# CyDAQ_schematic.net
KiCad netlist of a schematic drawn in EAGLE
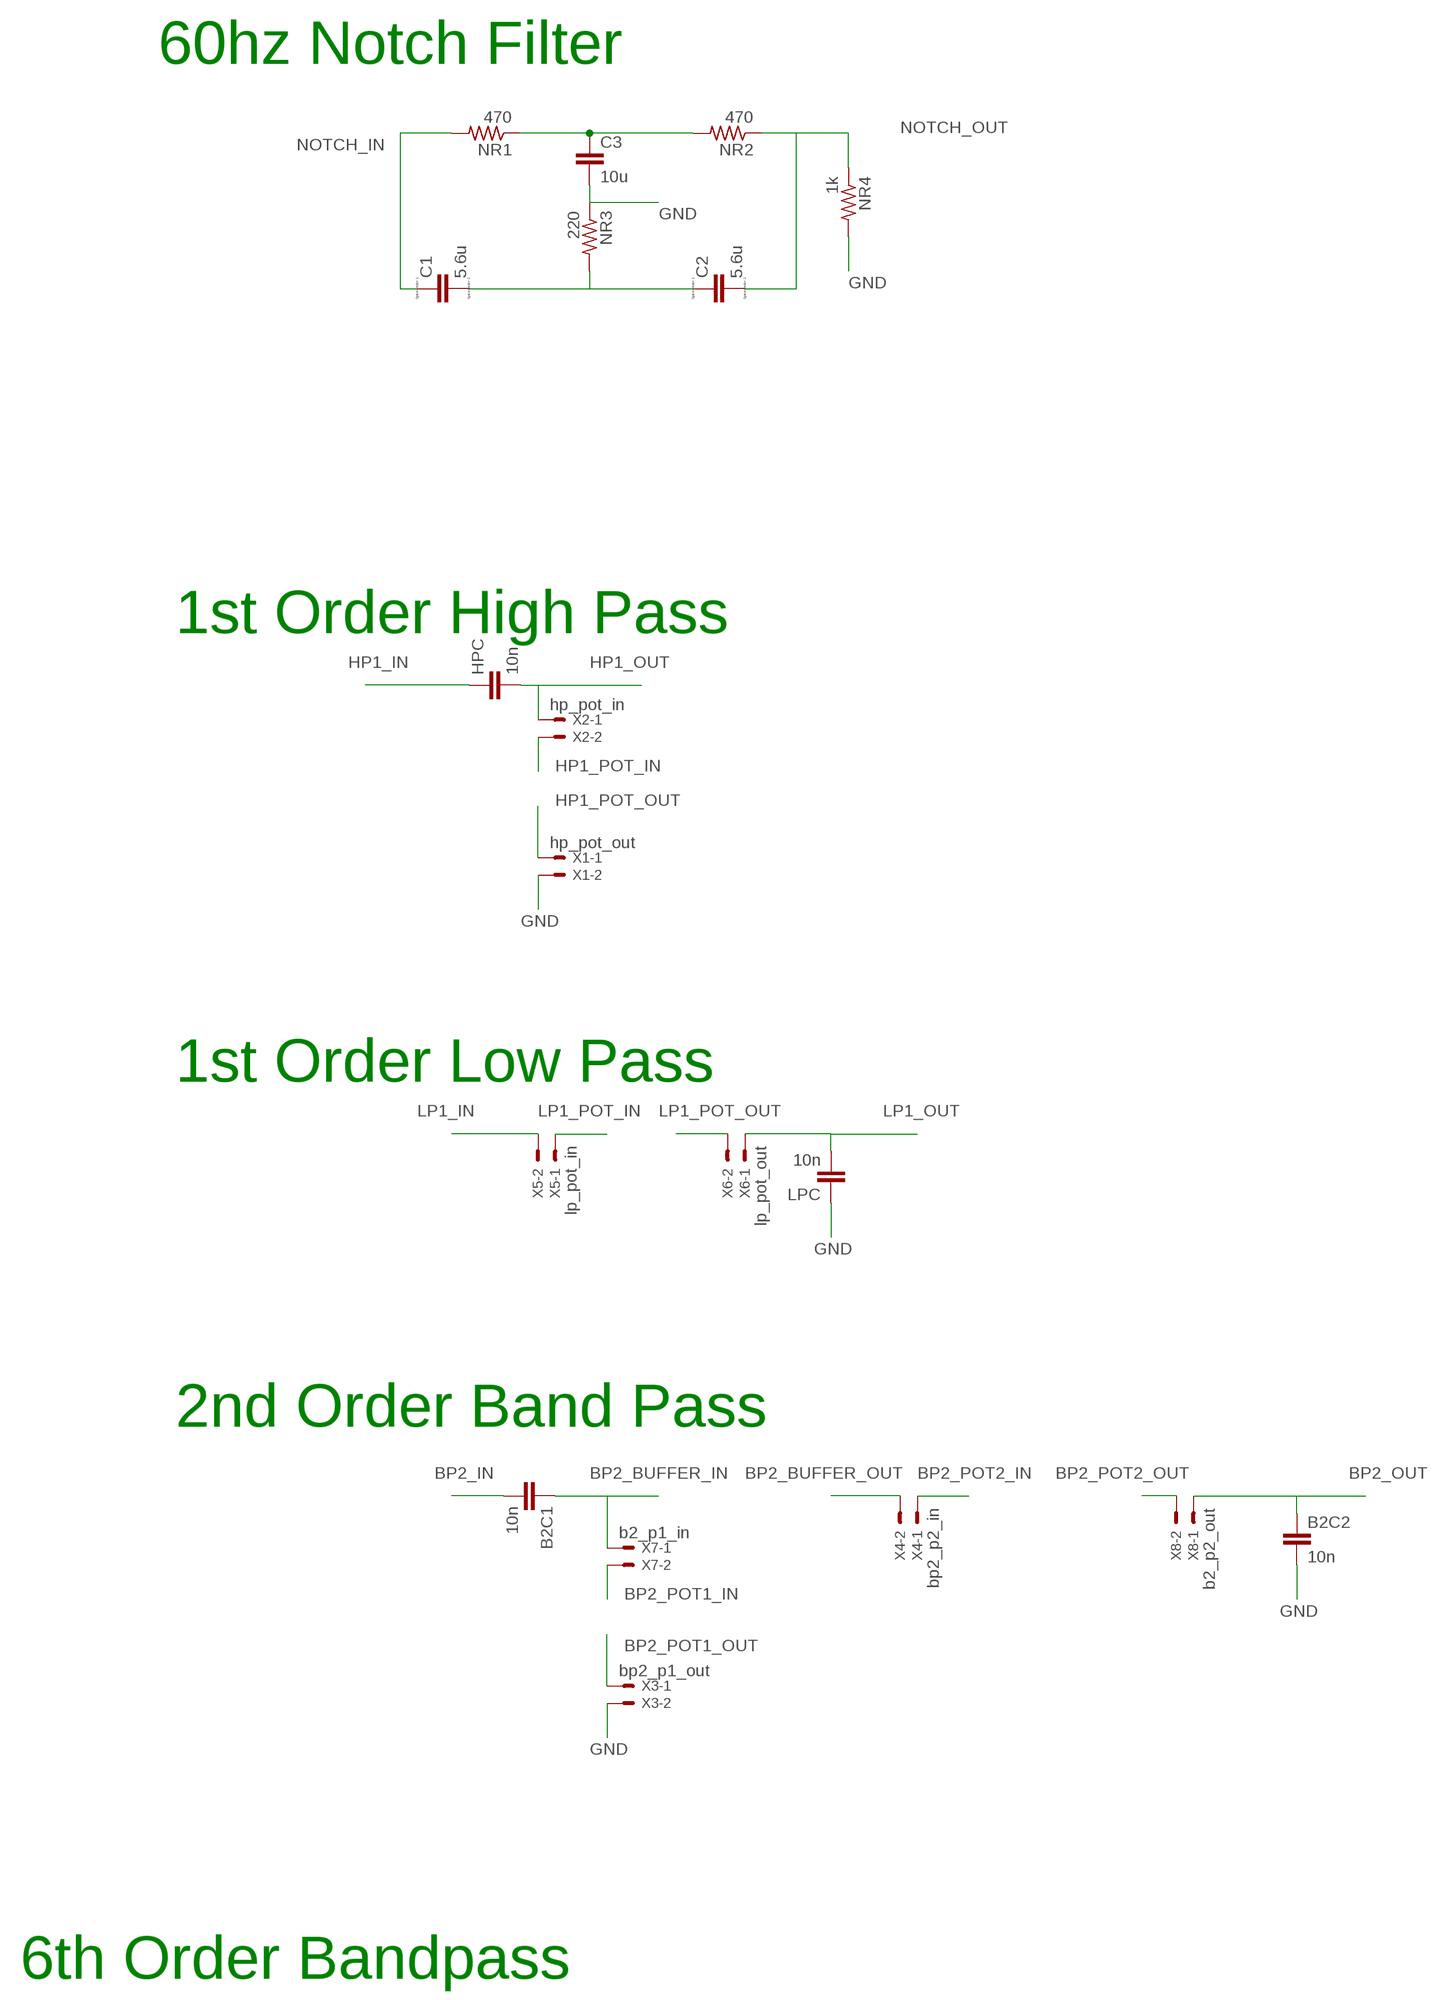
[diagram p0: schematic, sheet 1, part 1 of 3]
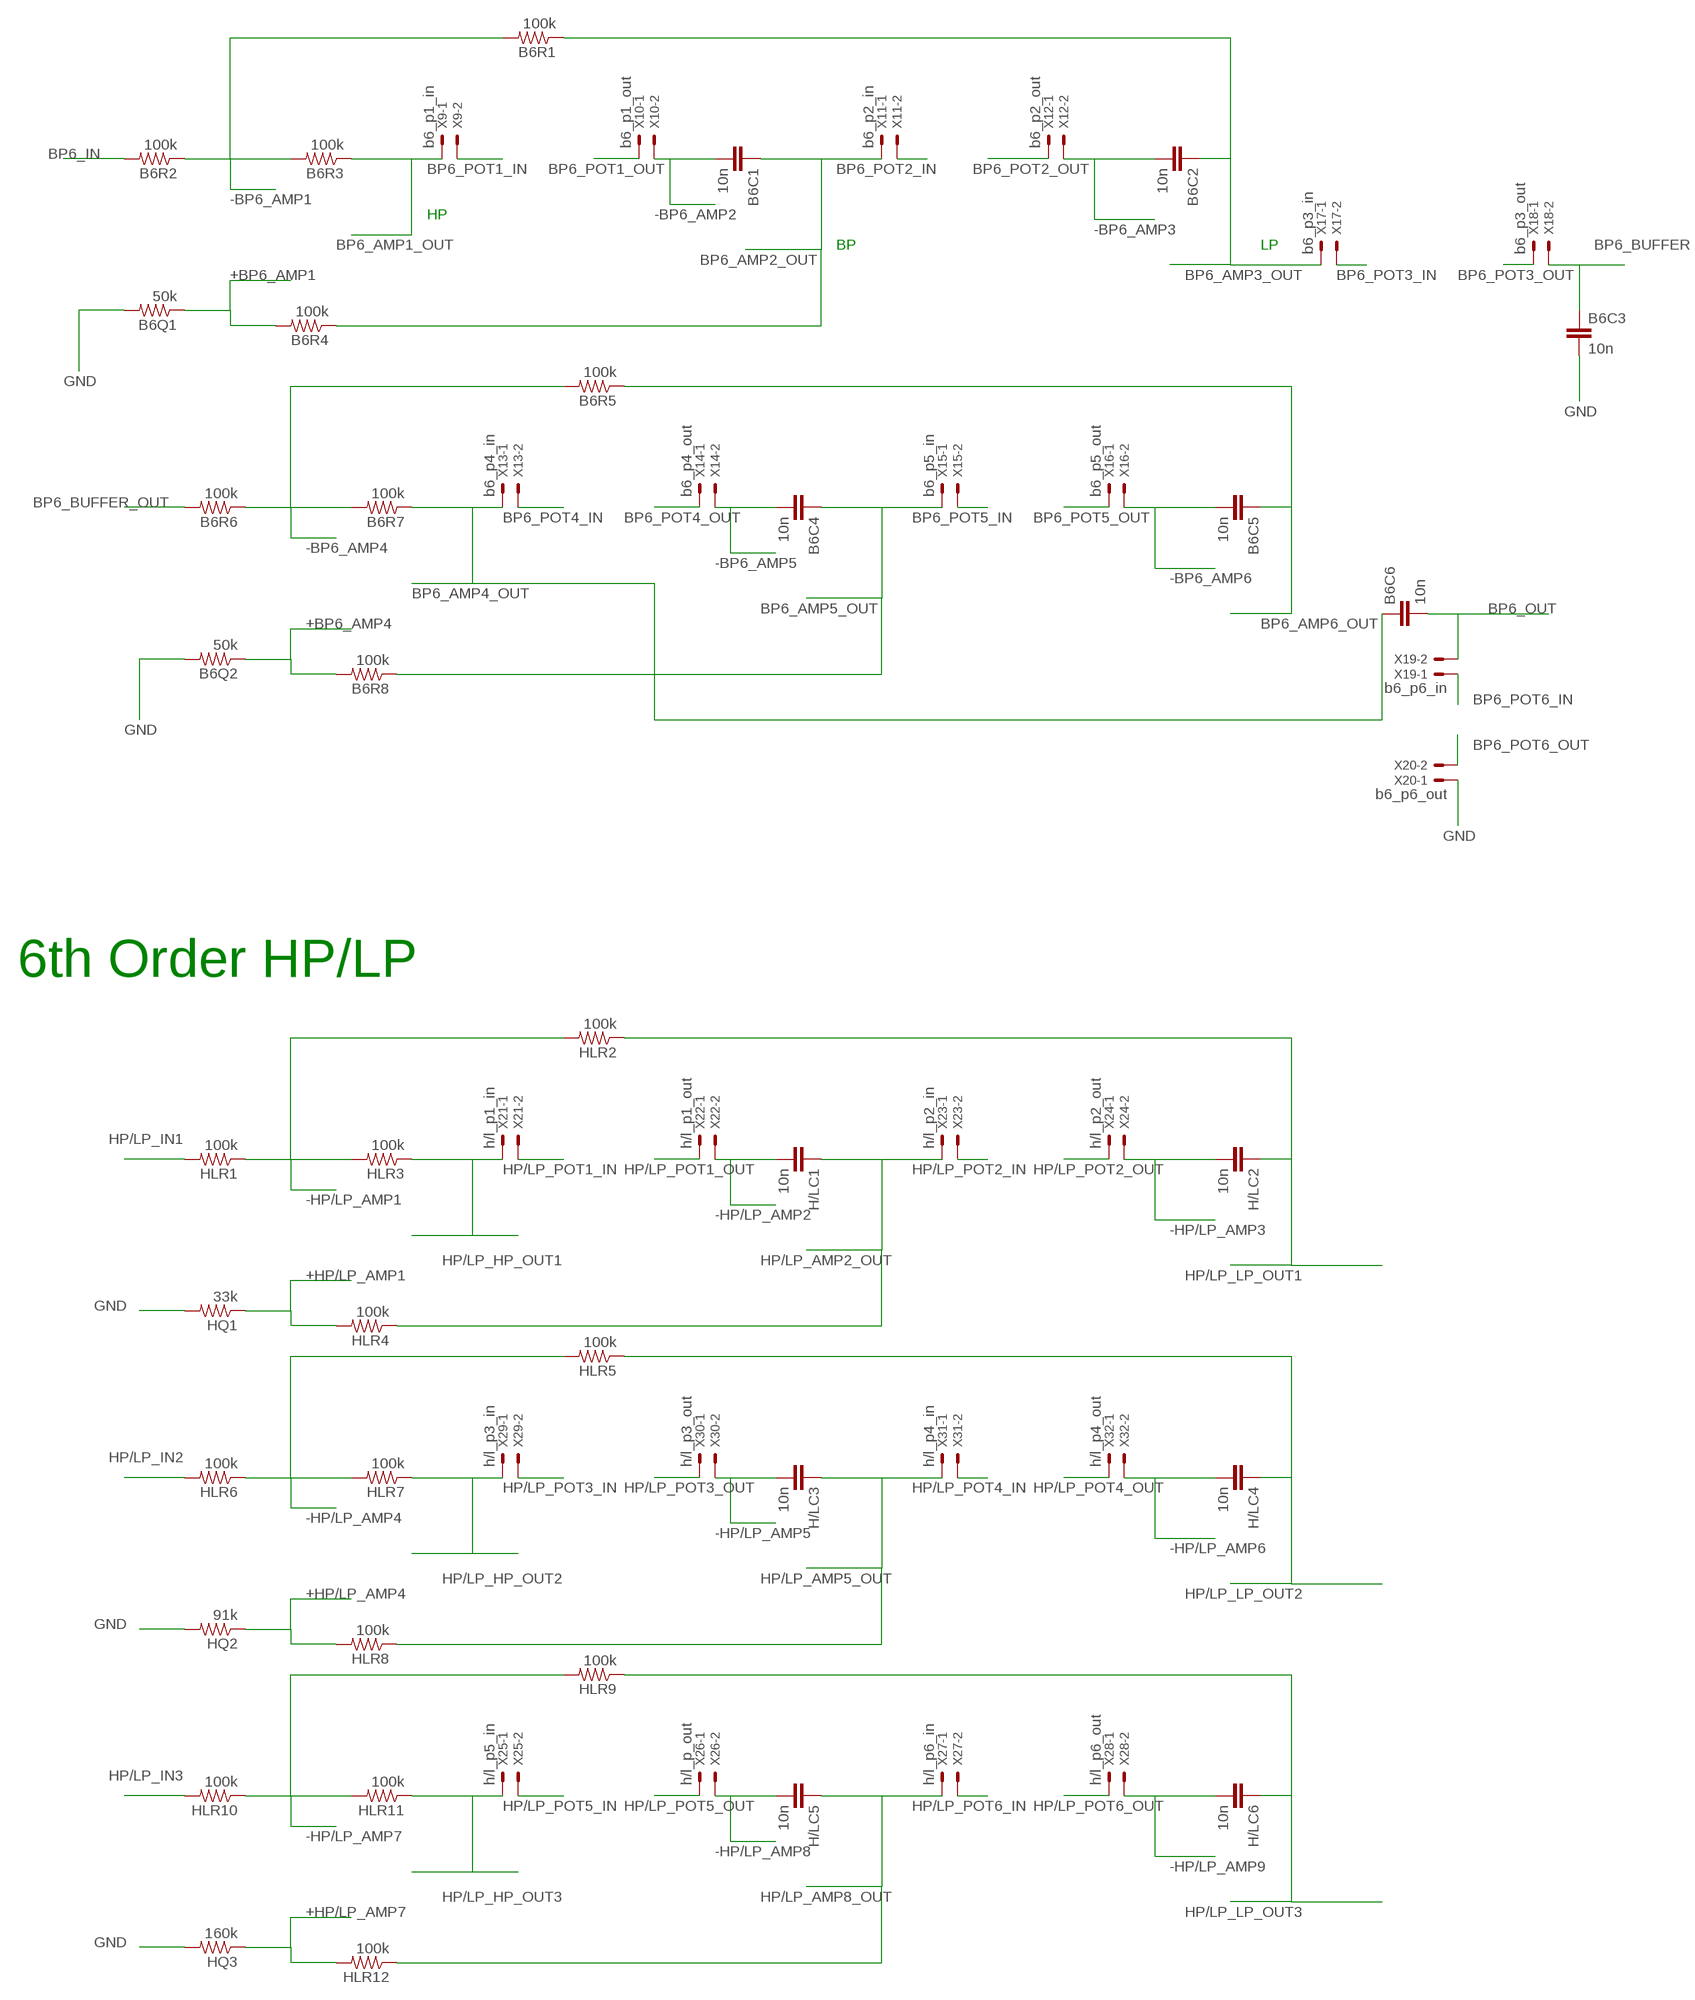
[diagram p1: schematic, sheet 1, part 2 of 3]
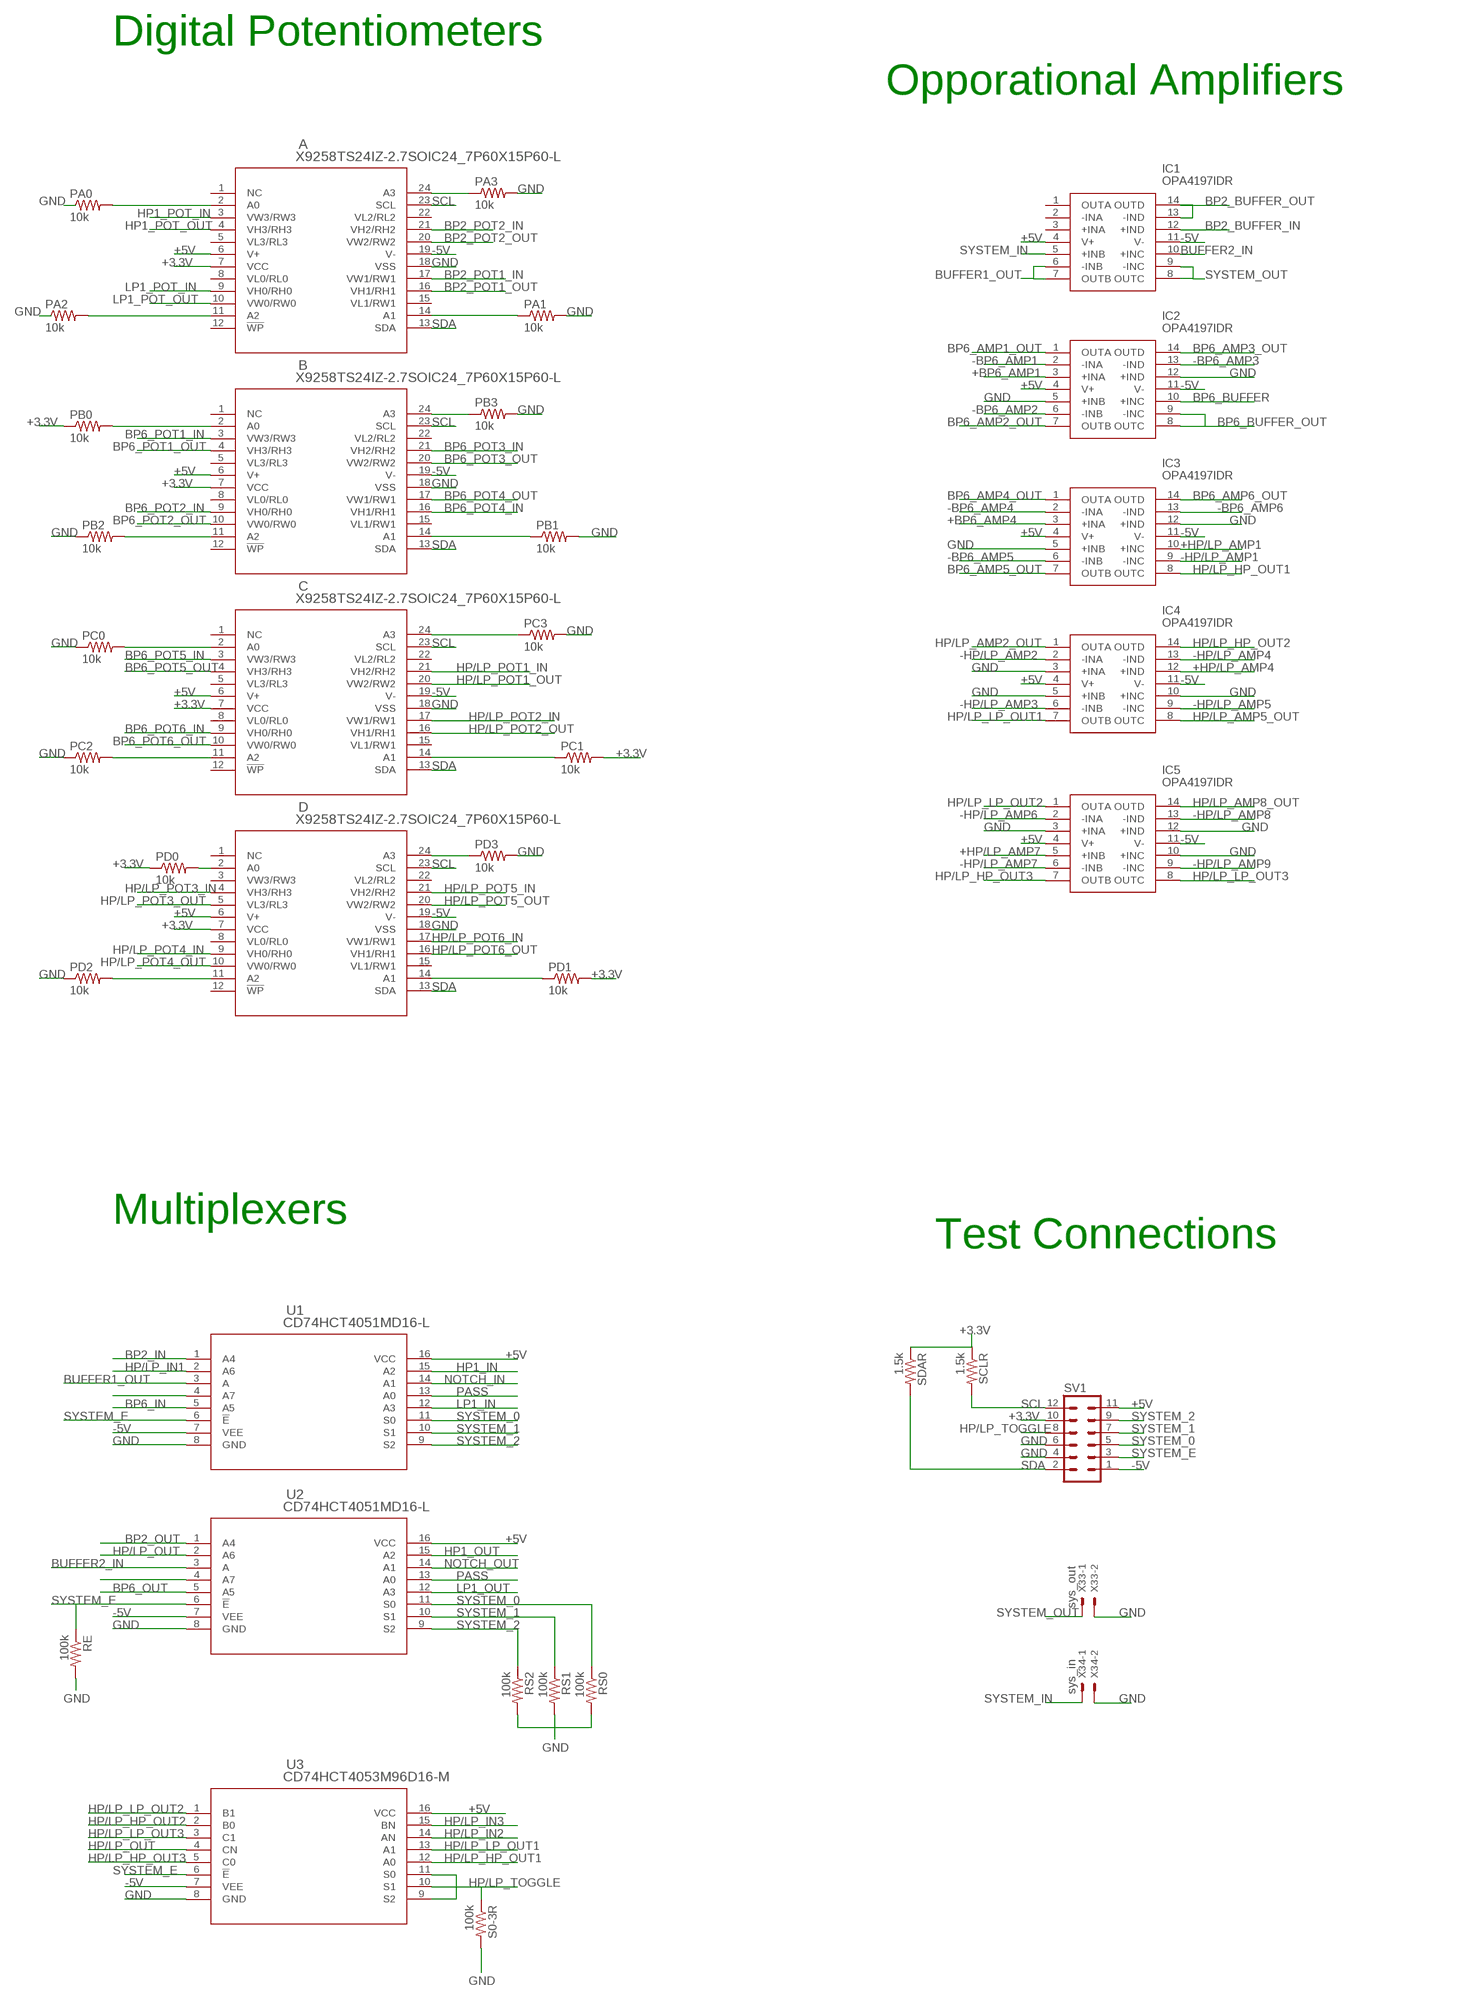
[diagram p2: schematic, sheet 1, part 3 of 3]

(export (version "E")
  (design (tool "Eeschema 10.0.6"))
  (components
    (comp (ref "A")
      (value "X9258TS24IZ-2.7SOIC24_7P60X15P60-L")
      (footprint "eagle-import:SOIC24_7P60X15P60-L")
      (fields (field (name "MANUFACTURER_PART_NUMBER") "X9258TS24IZ2.7"))
      (libsource (lib "eagle-import") (part "X9258TS24IZ-2.7SOIC24_7P60X15P60-L"))
    )
    (comp (ref "B")
      (value "X9258TS24IZ-2.7SOIC24_7P60X15P60-L")
      (footprint "eagle-import:SOIC24_7P60X15P60-L")
      (fields (field (name "MANUFACTURER_PART_NUMBER") "X9258TS24IZ2.7"))
      (libsource (lib "eagle-import") (part "X9258TS24IZ-2.7SOIC24_7P60X15P60-L"))
    )
    (comp (ref "B2C1")
      (value "10n")
      (footprint "eagle-import:C0805K")
      (libsource (lib "eagle-import") (part "C-EUC0805K"))
    )
    (comp (ref "B2C2")
      (value "10n")
      (footprint "eagle-import:C0805K")
      (libsource (lib "eagle-import") (part "C-EUC0805K"))
    )
    (comp (ref "B6C1")
      (value "10n")
      (footprint "eagle-import:C0805K")
      (libsource (lib "eagle-import") (part "C-EUC0805K"))
    )
    (comp (ref "B6C2")
      (value "10n")
      (footprint "eagle-import:C0805K")
      (libsource (lib "eagle-import") (part "C-EUC0805K"))
    )
    (comp (ref "B6C3")
      (value "10n")
      (footprint "eagle-import:C0805K")
      (libsource (lib "eagle-import") (part "C-EUC0805K"))
    )
    (comp (ref "B6C4")
      (value "10n")
      (footprint "eagle-import:C0805K")
      (libsource (lib "eagle-import") (part "C-EUC0805K"))
    )
    (comp (ref "B6C5")
      (value "10n")
      (footprint "eagle-import:C0805K")
      (libsource (lib "eagle-import") (part "C-EUC0805K"))
    )
    (comp (ref "B6C6")
      (value "10n")
      (footprint "eagle-import:C0805K")
      (libsource (lib "eagle-import") (part "C-EUC0805K"))
    )
    (comp (ref "B6Q1")
      (value "50k")
      (footprint "eagle-import:R0805W")
      (libsource (lib "eagle-import") (part "R-US_R0805W"))
    )
    (comp (ref "B6Q2")
      (value "50k")
      (footprint "eagle-import:R0805W")
      (libsource (lib "eagle-import") (part "R-US_R0805W"))
    )
    (comp (ref "B6R1")
      (value "100k")
      (footprint "eagle-import:R0805W")
      (libsource (lib "eagle-import") (part "R-US_R0805W"))
    )
    (comp (ref "B6R2")
      (value "100k")
      (footprint "eagle-import:R0805W")
      (libsource (lib "eagle-import") (part "R-US_R0805W"))
    )
    (comp (ref "B6R3")
      (value "100k")
      (footprint "eagle-import:R0805W")
      (libsource (lib "eagle-import") (part "R-US_R0805W"))
    )
    (comp (ref "B6R4")
      (value "100k")
      (footprint "eagle-import:R0805W")
      (libsource (lib "eagle-import") (part "R-US_R0805W"))
    )
    (comp (ref "B6R5")
      (value "100k")
      (footprint "eagle-import:R0805W")
      (libsource (lib "eagle-import") (part "R-US_R0805W"))
    )
    (comp (ref "B6R6")
      (value "100k")
      (footprint "eagle-import:R0805W")
      (libsource (lib "eagle-import") (part "R-US_R0805W"))
    )
    (comp (ref "B6R7")
      (value "100k")
      (footprint "eagle-import:R0805W")
      (libsource (lib "eagle-import") (part "R-US_R0805W"))
    )
    (comp (ref "B6R8")
      (value "100k")
      (footprint "eagle-import:R0805W")
      (libsource (lib "eagle-import") (part "R-US_R0805W"))
    )
    (comp (ref "C")
      (value "X9258TS24IZ-2.7SOIC24_7P60X15P60-L")
      (footprint "eagle-import:SOIC24_7P60X15P60-L")
      (fields (field (name "MANUFACTURER_PART_NUMBER") "X9258TS24IZ2.7"))
      (libsource (lib "eagle-import") (part "X9258TS24IZ-2.7SOIC24_7P60X15P60-L"))
    )
    (comp (ref "C1")
      (value "5.6u")
      (footprint "eagle-import:C1206")
      (libsource (lib "eagle-import") (part "CC1206"))
    )
    (comp (ref "C2")
      (value "5.6u")
      (footprint "eagle-import:C1206")
      (libsource (lib "eagle-import") (part "CC1206"))
    )
    (comp (ref "C3")
      (value "10u")
      (footprint "eagle-import:C2012")
      (libsource (lib "eagle-import") (part "C-EUC2012"))
    )
    (comp (ref "D")
      (value "X9258TS24IZ-2.7SOIC24_7P60X15P60-L")
      (footprint "eagle-import:SOIC24_7P60X15P60-L")
      (fields (field (name "MANUFACTURER_PART_NUMBER") "X9258TS24IZ2.7"))
      (libsource (lib "eagle-import") (part "X9258TS24IZ-2.7SOIC24_7P60X15P60-L"))
    )
    (comp (ref "H/LC1")
      (value "10n")
      (footprint "eagle-import:C0805K")
      (libsource (lib "eagle-import") (part "C-EUC0805K"))
    )
    (comp (ref "H/LC2")
      (value "10n")
      (footprint "eagle-import:C0805K")
      (libsource (lib "eagle-import") (part "C-EUC0805K"))
    )
    (comp (ref "H/LC3")
      (value "10n")
      (footprint "eagle-import:C0805K")
      (libsource (lib "eagle-import") (part "C-EUC0805K"))
    )
    (comp (ref "H/LC4")
      (value "10n")
      (footprint "eagle-import:C0805K")
      (libsource (lib "eagle-import") (part "C-EUC0805K"))
    )
    (comp (ref "H/LC5")
      (value "10n")
      (footprint "eagle-import:C0805K")
      (libsource (lib "eagle-import") (part "C-EUC0805K"))
    )
    (comp (ref "H/LC6")
      (value "10n")
      (footprint "eagle-import:C0805K")
      (libsource (lib "eagle-import") (part "C-EUC0805K"))
    )
    (comp (ref "HLR1")
      (value "100k")
      (footprint "eagle-import:R0805W")
      (libsource (lib "eagle-import") (part "R-US_R0805W"))
    )
    (comp (ref "HLR2")
      (value "100k")
      (footprint "eagle-import:R0805W")
      (libsource (lib "eagle-import") (part "R-US_R0805W"))
    )
    (comp (ref "HLR3")
      (value "100k")
      (footprint "eagle-import:R0805W")
      (libsource (lib "eagle-import") (part "R-US_R0805W"))
    )
    (comp (ref "HLR4")
      (value "100k")
      (footprint "eagle-import:R0805W")
      (libsource (lib "eagle-import") (part "R-US_R0805W"))
    )
    (comp (ref "HLR5")
      (value "100k")
      (footprint "eagle-import:R0805W")
      (libsource (lib "eagle-import") (part "R-US_R0805W"))
    )
    (comp (ref "HLR6")
      (value "100k")
      (footprint "eagle-import:R0805W")
      (libsource (lib "eagle-import") (part "R-US_R0805W"))
    )
    (comp (ref "HLR7")
      (value "100k")
      (footprint "eagle-import:R0805W")
      (libsource (lib "eagle-import") (part "R-US_R0805W"))
    )
    (comp (ref "HLR8")
      (value "100k")
      (footprint "eagle-import:R0805W")
      (libsource (lib "eagle-import") (part "R-US_R0805W"))
    )
    (comp (ref "HLR9")
      (value "100k")
      (footprint "eagle-import:R0805W")
      (libsource (lib "eagle-import") (part "R-US_R0805W"))
    )
    (comp (ref "HLR10")
      (value "100k")
      (footprint "eagle-import:R0805W")
      (libsource (lib "eagle-import") (part "R-US_R0805W"))
    )
    (comp (ref "HLR11")
      (value "100k")
      (footprint "eagle-import:R0805W")
      (libsource (lib "eagle-import") (part "R-US_R0805W"))
    )
    (comp (ref "HLR12")
      (value "100k")
      (footprint "eagle-import:R0805W")
      (libsource (lib "eagle-import") (part "R-US_R0805W"))
    )
    (comp (ref "HPC")
      (value "10n")
      (footprint "eagle-import:C0805K")
      (libsource (lib "eagle-import") (part "C-EUC0805K"))
    )
    (comp (ref "HQ1")
      (value "33k")
      (footprint "eagle-import:R0805W")
      (libsource (lib "eagle-import") (part "R-US_R0805W"))
    )
    (comp (ref "HQ2")
      (value "91k")
      (footprint "eagle-import:R0805W")
      (libsource (lib "eagle-import") (part "R-US_R0805W"))
    )
    (comp (ref "HQ3")
      (value "160k")
      (footprint "eagle-import:R0805W")
      (libsource (lib "eagle-import") (part "R-US_R0805W"))
    )
    (comp (ref "IC1")
      (value "OPA4197IDR")
      (footprint "eagle-import:SOIC127P600X175-14N")
      (fields (field (name "MOUSER_PART_NUMBER") "595-OPA4197IDR"))
      (libsource (lib "eagle-import") (part "OPA4197IDR"))
    )
    (comp (ref "IC2")
      (value "OPA4197IDR")
      (footprint "eagle-import:SOIC127P600X175-14N")
      (fields (field (name "MOUSER_PART_NUMBER") "595-OPA4197IDR"))
      (libsource (lib "eagle-import") (part "OPA4197IDR"))
    )
    (comp (ref "IC3")
      (value "OPA4197IDR")
      (footprint "eagle-import:SOIC127P600X175-14N")
      (fields (field (name "MOUSER_PART_NUMBER") "595-OPA4197IDR"))
      (libsource (lib "eagle-import") (part "OPA4197IDR"))
    )
    (comp (ref "IC4")
      (value "OPA4197IDR")
      (footprint "eagle-import:SOIC127P600X175-14N")
      (fields (field (name "MOUSER_PART_NUMBER") "595-OPA4197IDR"))
      (libsource (lib "eagle-import") (part "OPA4197IDR"))
    )
    (comp (ref "IC5")
      (value "OPA4197IDR")
      (footprint "eagle-import:SOIC127P600X175-14N")
      (fields (field (name "MOUSER_PART_NUMBER") "595-OPA4197IDR"))
      (libsource (lib "eagle-import") (part "OPA4197IDR"))
    )
    (comp (ref "LPC")
      (value "10n")
      (footprint "eagle-import:C0805K")
      (libsource (lib "eagle-import") (part "C-EUC0805K"))
    )
    (comp (ref "NR1")
      (value "470")
      (footprint "eagle-import:R0805W")
      (libsource (lib "eagle-import") (part "R-US_R0805W"))
    )
    (comp (ref "NR2")
      (value "470")
      (footprint "eagle-import:R0805W")
      (libsource (lib "eagle-import") (part "R-US_R0805W"))
    )
    (comp (ref "NR3")
      (value "220")
      (footprint "eagle-import:R0805W")
      (libsource (lib "eagle-import") (part "R-US_R0805W"))
    )
    (comp (ref "NR4")
      (value "1k")
      (footprint "eagle-import:R0805W")
      (libsource (lib "eagle-import") (part "R-US_R0805W"))
    )
    (comp (ref "PA0")
      (value "10k")
      (footprint "eagle-import:R0805W")
      (libsource (lib "eagle-import") (part "R-US_R0805W"))
    )
    (comp (ref "PA1")
      (value "10k")
      (footprint "eagle-import:R0805W")
      (libsource (lib "eagle-import") (part "R-US_R0805W"))
    )
    (comp (ref "PA2")
      (value "10k")
      (footprint "eagle-import:R0805W")
      (libsource (lib "eagle-import") (part "R-US_R0805W"))
    )
    (comp (ref "PA3")
      (value "10k")
      (footprint "eagle-import:R0805W")
      (libsource (lib "eagle-import") (part "R-US_R0805W"))
    )
    (comp (ref "PB0")
      (value "10k")
      (footprint "eagle-import:R0805W")
      (libsource (lib "eagle-import") (part "R-US_R0805W"))
    )
    (comp (ref "PB1")
      (value "10k")
      (footprint "eagle-import:R0805W")
      (libsource (lib "eagle-import") (part "R-US_R0805W"))
    )
    (comp (ref "PB2")
      (value "10k")
      (footprint "eagle-import:R0805W")
      (libsource (lib "eagle-import") (part "R-US_R0805W"))
    )
    (comp (ref "PB3")
      (value "10k")
      (footprint "eagle-import:R0805W")
      (libsource (lib "eagle-import") (part "R-US_R0805W"))
    )
    (comp (ref "PC0")
      (value "10k")
      (footprint "eagle-import:R0805W")
      (libsource (lib "eagle-import") (part "R-US_R0805W"))
    )
    (comp (ref "PC1")
      (value "10k")
      (footprint "eagle-import:R0805W")
      (libsource (lib "eagle-import") (part "R-US_R0805W"))
    )
    (comp (ref "PC2")
      (value "10k")
      (footprint "eagle-import:R0805W")
      (libsource (lib "eagle-import") (part "R-US_R0805W"))
    )
    (comp (ref "PC3")
      (value "10k")
      (footprint "eagle-import:R0805W")
      (libsource (lib "eagle-import") (part "R-US_R0805W"))
    )
    (comp (ref "PD0")
      (value "10k")
      (footprint "eagle-import:R0805W")
      (libsource (lib "eagle-import") (part "R-US_R0805W"))
    )
    (comp (ref "PD1")
      (value "10k")
      (footprint "eagle-import:R0805W")
      (libsource (lib "eagle-import") (part "R-US_R0805W"))
    )
    (comp (ref "PD2")
      (value "10k")
      (footprint "eagle-import:R0805W")
      (libsource (lib "eagle-import") (part "R-US_R0805W"))
    )
    (comp (ref "PD3")
      (value "10k")
      (footprint "eagle-import:R0805W")
      (libsource (lib "eagle-import") (part "R-US_R0805W"))
    )
    (comp (ref "RE")
      (value "100k")
      (footprint "eagle-import:R0805W")
      (libsource (lib "eagle-import") (part "R-US_R0805W"))
    )
    (comp (ref "RS0")
      (value "100k")
      (footprint "eagle-import:R0805W")
      (libsource (lib "eagle-import") (part "R-US_R0805W"))
    )
    (comp (ref "RS1")
      (value "100k")
      (footprint "eagle-import:R0805W")
      (libsource (lib "eagle-import") (part "R-US_R0805W"))
    )
    (comp (ref "RS2")
      (value "100k")
      (footprint "eagle-import:R0805W")
      (libsource (lib "eagle-import") (part "R-US_R0805W"))
    )
    (comp (ref "S0-3R")
      (value "100k")
      (footprint "eagle-import:R0805W")
      (libsource (lib "eagle-import") (part "R-US_R0805W"))
    )
    (comp (ref "SCLR")
      (value "1.5k")
      (footprint "eagle-import:R0805W")
      (libsource (lib "eagle-import") (part "R-US_R0805W"))
    )
    (comp (ref "SDAR")
      (value "1.5k")
      (footprint "eagle-import:R0805W")
      (libsource (lib "eagle-import") (part "R-US_R0805W"))
    )
    (comp (ref "SV1")
      (value "MA06-2")
      (footprint "eagle-import:MA06-2")
      (libsource (lib "eagle-import") (part "MA06-2"))
    )
    (comp (ref "U1")
      (value "CD74HCT4051MD16-L")
      (footprint "eagle-import:D16-L")
      (fields (field (name "MANUFACTURER_PART_NUMBER") "CD74HCT4051M"))
      (libsource (lib "eagle-import") (part "CD74HCT4051MD16-L"))
    )
    (comp (ref "U2")
      (value "CD74HCT4051MD16-L")
      (footprint "eagle-import:D16-L")
      (fields (field (name "MANUFACTURER_PART_NUMBER") "CD74HCT4051M"))
      (libsource (lib "eagle-import") (part "CD74HCT4051MD16-L"))
    )
    (comp (ref "U3")
      (value "CD74HCT4053M96D16-M")
      (footprint "eagle-import:D16-M")
      (fields (field (name "MANUFACTURER_PART_NUMBER") "CD74HCT4053M96"))
      (libsource (lib "eagle-import") (part "CD74HCT4053M96D16-M"))
    )
    (comp (ref "X1")
      (value "hp_pot_out")
      (footprint "eagle-import:22-23-2021")
      (fields (field (name "MF") "MOLEX") (field (name "MPN") "22-23-2021"))
      (libsource (lib "eagle-import") (part "22-23-2021"))
    )
    (comp (ref "X2")
      (value "hp_pot_in")
      (footprint "eagle-import:22-23-2021")
      (fields (field (name "MF") "MOLEX") (field (name "MPN") "22-23-2021"))
      (libsource (lib "eagle-import") (part "22-23-2021"))
    )
    (comp (ref "X3")
      (value "bp2_p1_out")
      (footprint "eagle-import:22-23-2021")
      (fields (field (name "MF") "MOLEX") (field (name "MPN") "22-23-2021"))
      (libsource (lib "eagle-import") (part "22-23-2021"))
    )
    (comp (ref "X4")
      (value "bp2_p2_in")
      (footprint "eagle-import:22-23-2021")
      (fields (field (name "MF") "MOLEX") (field (name "MPN") "22-23-2021"))
      (libsource (lib "eagle-import") (part "22-23-2021"))
    )
    (comp (ref "X5")
      (value "lp_pot_in")
      (footprint "eagle-import:22-23-2021")
      (fields (field (name "MF") "MOLEX") (field (name "MPN") "22-23-2021"))
      (libsource (lib "eagle-import") (part "22-23-2021"))
    )
    (comp (ref "X6")
      (value "lp_pot_out")
      (footprint "eagle-import:22-23-2021")
      (fields (field (name "MF") "MOLEX") (field (name "MPN") "22-23-2021"))
      (libsource (lib "eagle-import") (part "22-23-2021"))
    )
    (comp (ref "X7")
      (value "b2_p1_in")
      (footprint "eagle-import:22-23-2021")
      (fields (field (name "MF") "MOLEX") (field (name "MPN") "22-23-2021"))
      (libsource (lib "eagle-import") (part "22-23-2021"))
    )
    (comp (ref "X8")
      (value "b2_p2_out")
      (footprint "eagle-import:22-23-2021")
      (fields (field (name "MF") "MOLEX") (field (name "MPN") "22-23-2021"))
      (libsource (lib "eagle-import") (part "22-23-2021"))
    )
    (comp (ref "X9")
      (value "b6_p1_in")
      (footprint "eagle-import:22-23-2021")
      (fields (field (name "MF") "MOLEX") (field (name "MPN") "22-23-2021"))
      (libsource (lib "eagle-import") (part "22-23-2021"))
    )
    (comp (ref "X10")
      (value "b6_p1_out")
      (footprint "eagle-import:22-23-2021")
      (fields (field (name "MF") "MOLEX") (field (name "MPN") "22-23-2021"))
      (libsource (lib "eagle-import") (part "22-23-2021"))
    )
    (comp (ref "X11")
      (value "b6_p2_in")
      (footprint "eagle-import:22-23-2021")
      (fields (field (name "MF") "MOLEX") (field (name "MPN") "22-23-2021"))
      (libsource (lib "eagle-import") (part "22-23-2021"))
    )
    (comp (ref "X12")
      (value "b6_p2_out")
      (footprint "eagle-import:22-23-2021")
      (fields (field (name "MF") "MOLEX") (field (name "MPN") "22-23-2021"))
      (libsource (lib "eagle-import") (part "22-23-2021"))
    )
    (comp (ref "X13")
      (value "b6_p4_in")
      (footprint "eagle-import:22-23-2021")
      (fields (field (name "MF") "MOLEX") (field (name "MPN") "22-23-2021"))
      (libsource (lib "eagle-import") (part "22-23-2021"))
    )
    (comp (ref "X14")
      (value "b6_p4_out")
      (footprint "eagle-import:22-23-2021")
      (fields (field (name "MF") "MOLEX") (field (name "MPN") "22-23-2021"))
      (libsource (lib "eagle-import") (part "22-23-2021"))
    )
    (comp (ref "X15")
      (value "b6_p5_in")
      (footprint "eagle-import:22-23-2021")
      (fields (field (name "MF") "MOLEX") (field (name "MPN") "22-23-2021"))
      (libsource (lib "eagle-import") (part "22-23-2021"))
    )
    (comp (ref "X16")
      (value "b6_p5_out")
      (footprint "eagle-import:22-23-2021")
      (fields (field (name "MF") "MOLEX") (field (name "MPN") "22-23-2021"))
      (libsource (lib "eagle-import") (part "22-23-2021"))
    )
    (comp (ref "X17")
      (value "b6_p3_in")
      (footprint "eagle-import:22-23-2021")
      (fields (field (name "MF") "MOLEX") (field (name "MPN") "22-23-2021"))
      (libsource (lib "eagle-import") (part "22-23-2021"))
    )
    (comp (ref "X18")
      (value "b6_p3_out")
      (footprint "eagle-import:22-23-2021")
      (fields (field (name "MF") "MOLEX") (field (name "MPN") "22-23-2021"))
      (libsource (lib "eagle-import") (part "22-23-2021"))
    )
    (comp (ref "X19")
      (value "b6_p6_in")
      (footprint "eagle-import:22-23-2021")
      (fields (field (name "MF") "MOLEX") (field (name "MPN") "22-23-2021"))
      (libsource (lib "eagle-import") (part "22-23-2021"))
    )
    (comp (ref "X20")
      (value "b6_p6_out")
      (footprint "eagle-import:22-23-2021")
      (fields (field (name "MF") "MOLEX") (field (name "MPN") "22-23-2021"))
      (libsource (lib "eagle-import") (part "22-23-2021"))
    )
    (comp (ref "X21")
      (value "h/l_p1_in")
      (footprint "eagle-import:22-23-2021")
      (fields (field (name "MF") "MOLEX") (field (name "MPN") "22-23-2021"))
      (libsource (lib "eagle-import") (part "22-23-2021"))
    )
    (comp (ref "X22")
      (value "h/l_p1_out")
      (footprint "eagle-import:22-23-2021")
      (fields (field (name "MF") "MOLEX") (field (name "MPN") "22-23-2021"))
      (libsource (lib "eagle-import") (part "22-23-2021"))
    )
    (comp (ref "X23")
      (value "h/l_p2_in")
      (footprint "eagle-import:22-23-2021")
      (fields (field (name "MF") "MOLEX") (field (name "MPN") "22-23-2021"))
      (libsource (lib "eagle-import") (part "22-23-2021"))
    )
    (comp (ref "X24")
      (value "h/l_p2_out")
      (footprint "eagle-import:22-23-2021")
      (fields (field (name "MF") "MOLEX") (field (name "MPN") "22-23-2021"))
      (libsource (lib "eagle-import") (part "22-23-2021"))
    )
    (comp (ref "X25")
      (value "h/l_p5_in")
      (footprint "eagle-import:22-23-2021")
      (fields (field (name "MF") "MOLEX") (field (name "MPN") "22-23-2021"))
      (libsource (lib "eagle-import") (part "22-23-2021"))
    )
    (comp (ref "X26")
      (value "h/l_p_out")
      (footprint "eagle-import:22-23-2021")
      (fields (field (name "MF") "MOLEX") (field (name "MPN") "22-23-2021"))
      (libsource (lib "eagle-import") (part "22-23-2021"))
    )
    (comp (ref "X27")
      (value "h/l_p6_in")
      (footprint "eagle-import:22-23-2021")
      (fields (field (name "MF") "MOLEX") (field (name "MPN") "22-23-2021"))
      (libsource (lib "eagle-import") (part "22-23-2021"))
    )
    (comp (ref "X28")
      (value "h/l_p6_out")
      (footprint "eagle-import:22-23-2021")
      (fields (field (name "MF") "MOLEX") (field (name "MPN") "22-23-2021"))
      (libsource (lib "eagle-import") (part "22-23-2021"))
    )
    (comp (ref "X29")
      (value "h/l_p3_in")
      (footprint "eagle-import:22-23-2021")
      (fields (field (name "MF") "MOLEX") (field (name "MPN") "22-23-2021"))
      (libsource (lib "eagle-import") (part "22-23-2021"))
    )
    (comp (ref "X30")
      (value "h/l_p3_out")
      (footprint "eagle-import:22-23-2021")
      (fields (field (name "MF") "MOLEX") (field (name "MPN") "22-23-2021"))
      (libsource (lib "eagle-import") (part "22-23-2021"))
    )
    (comp (ref "X31")
      (value "h/l_p4_in")
      (footprint "eagle-import:22-23-2021")
      (fields (field (name "MF") "MOLEX") (field (name "MPN") "22-23-2021"))
      (libsource (lib "eagle-import") (part "22-23-2021"))
    )
    (comp (ref "X32")
      (value "h/l_p4_out")
      (footprint "eagle-import:22-23-2021")
      (fields (field (name "MF") "MOLEX") (field (name "MPN") "22-23-2021"))
      (libsource (lib "eagle-import") (part "22-23-2021"))
    )
    (comp (ref "X33")
      (value "sys_out")
      (footprint "eagle-import:22-23-2021")
      (fields (field (name "MF") "MOLEX") (field (name "MPN") "22-23-2021"))
      (libsource (lib "eagle-import") (part "22-23-2021"))
    )
    (comp (ref "X34")
      (value "sys_in")
      (footprint "eagle-import:22-23-2021")
      (fields (field (name "MF") "MOLEX") (field (name "MPN") "22-23-2021"))
      (libsource (lib "eagle-import") (part "22-23-2021"))
    )
  )
  (nets
    (net (code "1") (name "/+3.3V") (class "Default")
      (node (ref "A") (pin "7") (pinfunction "VCC_7") (pintype "power_in"))
      (node (ref "B") (pin "7") (pinfunction "VCC_7") (pintype "power_in"))
      (node (ref "C") (pin "7") (pinfunction "VCC_7") (pintype "power_in"))
      (node (ref "D") (pin "7") (pinfunction "VCC_7") (pintype "power_in"))
      (node (ref "PB0") (pin "1") (pinfunction "1_1") (pintype "passive"))
      (node (ref "PC1") (pin "2") (pinfunction "2_2") (pintype "passive"))
      (node (ref "PD0") (pin "1") (pinfunction "1_1") (pintype "passive"))
      (node (ref "PD1") (pin "2") (pinfunction "2_2") (pintype "passive"))
      (node (ref "SCLR") (pin "1") (pinfunction "1_1") (pintype "passive"))
      (node (ref "SDAR") (pin "1") (pinfunction "1_1") (pintype "passive"))
      (node (ref "SV1") (pin "10") (pinfunction "10_10") (pintype "passive"))
    )
    (net (code "2") (name "/+5V") (class "Default")
      (node (ref "A") (pin "6") (pinfunction "V+_6") (pintype "power_in"))
      (node (ref "B") (pin "6") (pinfunction "V+_6") (pintype "power_in"))
      (node (ref "C") (pin "6") (pinfunction "V+_6") (pintype "power_in"))
      (node (ref "D") (pin "6") (pinfunction "V+_6") (pintype "power_in"))
      (node (ref "IC1") (pin "4") (pinfunction "V+_4") (pintype "power_in"))
      (node (ref "IC2") (pin "4") (pinfunction "V+_4") (pintype "power_in"))
      (node (ref "IC3") (pin "4") (pinfunction "V+_4") (pintype "power_in"))
      (node (ref "IC4") (pin "4") (pinfunction "V+_4") (pintype "power_in"))
      (node (ref "IC5") (pin "4") (pinfunction "V+_4") (pintype "power_in"))
      (node (ref "SV1") (pin "11") (pinfunction "11_11") (pintype "passive"))
      (node (ref "U1") (pin "16") (pinfunction "VCC_16") (pintype "power_in"))
      (node (ref "U2") (pin "16") (pinfunction "VCC_16") (pintype "power_in"))
      (node (ref "U3") (pin "16") (pinfunction "VCC_16") (pintype "power_in"))
    )
    (net (code "3") (name "/+BP6_AMP1") (class "Default")
      (node (ref "B6Q1") (pin "1") (pinfunction "1_1") (pintype "passive"))
      (node (ref "B6R4") (pin "2") (pinfunction "2_2") (pintype "passive"))
      (node (ref "IC2") (pin "3") (pinfunction "+INA_3") (pintype "input"))
    )
    (net (code "4") (name "/+BP6_AMP4") (class "Default")
      (node (ref "B6Q2") (pin "1") (pinfunction "1_1") (pintype "passive"))
      (node (ref "B6R8") (pin "2") (pinfunction "2_2") (pintype "passive"))
      (node (ref "IC3") (pin "3") (pinfunction "+INA_3") (pintype "input"))
    )
    (net (code "5") (name "/+HP{slash}LP_AMP1") (class "Default")
      (node (ref "HLR4") (pin "2") (pinfunction "2_2") (pintype "passive"))
      (node (ref "HQ1") (pin "1") (pinfunction "1_1") (pintype "passive"))
      (node (ref "IC3") (pin "10") (pinfunction "+INC_10") (pintype "input"))
    )
    (net (code "6") (name "/+HP{slash}LP_AMP4") (class "Default")
      (node (ref "HLR8") (pin "2") (pinfunction "2_2") (pintype "passive"))
      (node (ref "HQ2") (pin "1") (pinfunction "1_1") (pintype "passive"))
      (node (ref "IC4") (pin "12") (pinfunction "+IND_12") (pintype "input"))
    )
    (net (code "7") (name "/+HP{slash}LP_AMP7") (class "Default")
      (node (ref "HLR12") (pin "2") (pinfunction "2_2") (pintype "passive"))
      (node (ref "HQ3") (pin "1") (pinfunction "1_1") (pintype "passive"))
      (node (ref "IC5") (pin "5") (pinfunction "+INB_5") (pintype "input"))
    )
    (net (code "8") (name "/-5V") (class "Default")
      (node (ref "A") (pin "19") (pinfunction "V-_19") (pintype "power_in"))
      (node (ref "B") (pin "19") (pinfunction "V-_19") (pintype "power_in"))
      (node (ref "C") (pin "19") (pinfunction "V-_19") (pintype "power_in"))
      (node (ref "D") (pin "19") (pinfunction "V-_19") (pintype "power_in"))
      (node (ref "IC1") (pin "11") (pinfunction "V-_11") (pintype "power_in"))
      (node (ref "IC2") (pin "11") (pinfunction "V-_11") (pintype "power_in"))
      (node (ref "IC3") (pin "11") (pinfunction "V-_11") (pintype "power_in"))
      (node (ref "IC4") (pin "11") (pinfunction "V-_11") (pintype "power_in"))
      (node (ref "IC5") (pin "11") (pinfunction "V-_11") (pintype "power_in"))
      (node (ref "SV1") (pin "1") (pinfunction "1_1") (pintype "passive"))
      (node (ref "U1") (pin "7") (pinfunction "VEE_7") (pintype "power_in"))
      (node (ref "U2") (pin "7") (pinfunction "VEE_7") (pintype "power_in"))
      (node (ref "U3") (pin "7") (pinfunction "VEE_7") (pintype "power_in"))
    )
    (net (code "9") (name "/-BP6_AMP1") (class "Default")
      (node (ref "B6R1") (pin "2") (pinfunction "2_2") (pintype "passive"))
      (node (ref "B6R2") (pin "1") (pinfunction "1_1") (pintype "passive"))
      (node (ref "B6R3") (pin "2") (pinfunction "2_2") (pintype "passive"))
      (node (ref "IC2") (pin "2") (pinfunction "-INA_2") (pintype "input"))
    )
    (net (code "10") (name "/-BP6_AMP2") (class "Default")
      (node (ref "B6C1") (pin "2") (pinfunction "2_2") (pintype "passive"))
      (node (ref "IC2") (pin "6") (pinfunction "-INB_6") (pintype "input"))
      (node (ref "X10") (pin "2") (pinfunction "S_2") (pintype "passive"))
    )
    (net (code "11") (name "/-BP6_AMP3") (class "Default")
      (node (ref "B6C2") (pin "2") (pinfunction "2_2") (pintype "passive"))
      (node (ref "IC2") (pin "13") (pinfunction "-IND_13") (pintype "input"))
      (node (ref "X12") (pin "2") (pinfunction "S_2") (pintype "passive"))
    )
    (net (code "12") (name "/-BP6_AMP4") (class "Default")
      (node (ref "B6R5") (pin "2") (pinfunction "2_2") (pintype "passive"))
      (node (ref "B6R6") (pin "1") (pinfunction "1_1") (pintype "passive"))
      (node (ref "B6R7") (pin "2") (pinfunction "2_2") (pintype "passive"))
      (node (ref "IC3") (pin "2") (pinfunction "-INA_2") (pintype "input"))
    )
    (net (code "13") (name "/-BP6_AMP5") (class "Default")
      (node (ref "B6C4") (pin "2") (pinfunction "2_2") (pintype "passive"))
      (node (ref "IC3") (pin "6") (pinfunction "-INB_6") (pintype "input"))
      (node (ref "X14") (pin "2") (pinfunction "S_2") (pintype "passive"))
    )
    (net (code "14") (name "/-BP6_AMP6") (class "Default")
      (node (ref "B6C5") (pin "2") (pinfunction "2_2") (pintype "passive"))
      (node (ref "IC3") (pin "13") (pinfunction "-IND_13") (pintype "input"))
      (node (ref "X16") (pin "2") (pinfunction "S_2") (pintype "passive"))
    )
    (net (code "15") (name "/-HP{slash}LP_AMP1") (class "Default")
      (node (ref "HLR1") (pin "1") (pinfunction "1_1") (pintype "passive"))
      (node (ref "HLR2") (pin "2") (pinfunction "2_2") (pintype "passive"))
      (node (ref "HLR3") (pin "2") (pinfunction "2_2") (pintype "passive"))
      (node (ref "IC3") (pin "9") (pinfunction "-INC_9") (pintype "input"))
    )
    (net (code "16") (name "/-HP{slash}LP_AMP2") (class "Default")
      (node (ref "H/LC1") (pin "2") (pinfunction "2_2") (pintype "passive"))
      (node (ref "IC4") (pin "2") (pinfunction "-INA_2") (pintype "input"))
      (node (ref "X22") (pin "2") (pinfunction "S_2") (pintype "passive"))
    )
    (net (code "17") (name "/-HP{slash}LP_AMP3") (class "Default")
      (node (ref "H/LC2") (pin "2") (pinfunction "2_2") (pintype "passive"))
      (node (ref "IC4") (pin "6") (pinfunction "-INB_6") (pintype "input"))
      (node (ref "X24") (pin "2") (pinfunction "S_2") (pintype "passive"))
    )
    (net (code "18") (name "/-HP{slash}LP_AMP4") (class "Default")
      (node (ref "HLR5") (pin "2") (pinfunction "2_2") (pintype "passive"))
      (node (ref "HLR6") (pin "1") (pinfunction "1_1") (pintype "passive"))
      (node (ref "HLR7") (pin "2") (pinfunction "2_2") (pintype "passive"))
      (node (ref "IC4") (pin "13") (pinfunction "-IND_13") (pintype "input"))
    )
    (net (code "19") (name "/-HP{slash}LP_AMP5") (class "Default")
      (node (ref "H/LC3") (pin "2") (pinfunction "2_2") (pintype "passive"))
      (node (ref "IC4") (pin "9") (pinfunction "-INC_9") (pintype "input"))
      (node (ref "X30") (pin "2") (pinfunction "S_2") (pintype "passive"))
    )
    (net (code "20") (name "/-HP{slash}LP_AMP6") (class "Default")
      (node (ref "H/LC4") (pin "2") (pinfunction "2_2") (pintype "passive"))
      (node (ref "IC5") (pin "2") (pinfunction "-INA_2") (pintype "input"))
      (node (ref "X32") (pin "2") (pinfunction "S_2") (pintype "passive"))
    )
    (net (code "21") (name "/-HP{slash}LP_AMP7") (class "Default")
      (node (ref "HLR10") (pin "1") (pinfunction "1_1") (pintype "passive"))
      (node (ref "HLR11") (pin "2") (pinfunction "2_2") (pintype "passive"))
      (node (ref "HLR9") (pin "2") (pinfunction "2_2") (pintype "passive"))
      (node (ref "IC5") (pin "6") (pinfunction "-INB_6") (pintype "input"))
    )
    (net (code "22") (name "/-HP{slash}LP_AMP8") (class "Default")
      (node (ref "H/LC5") (pin "2") (pinfunction "2_2") (pintype "passive"))
      (node (ref "IC5") (pin "13") (pinfunction "-IND_13") (pintype "input"))
      (node (ref "X26") (pin "2") (pinfunction "S_2") (pintype "passive"))
    )
    (net (code "23") (name "/-HP{slash}LP_AMP9") (class "Default")
      (node (ref "H/LC6") (pin "2") (pinfunction "2_2") (pintype "passive"))
      (node (ref "IC5") (pin "9") (pinfunction "-INC_9") (pintype "input"))
      (node (ref "X28") (pin "2") (pinfunction "S_2") (pintype "passive"))
    )
    (net (code "24") (name "/BP2_BUFFER_IN") (class "Default")
      (node (ref "B2C1") (pin "1") (pinfunction "1_1") (pintype "passive"))
      (node (ref "IC1") (pin "12") (pinfunction "+IND_12") (pintype "input"))
      (node (ref "X7") (pin "1") (pinfunction "S_1") (pintype "passive"))
    )
    (net (code "25") (name "/BP2_BUFFER_OUT") (class "Default")
      (node (ref "IC1") (pin "13") (pinfunction "-IND_13") (pintype "input"))
      (node (ref "IC1") (pin "14") (pinfunction "OUTD_14") (pintype "output"))
      (node (ref "X4") (pin "2") (pinfunction "S_2") (pintype "passive"))
    )
    (net (code "26") (name "/BP2_IN") (class "Default")
      (node (ref "B2C1") (pin "2") (pinfunction "2_2") (pintype "passive"))
      (node (ref "U1") (pin "1") (pinfunction "A4_1") (pintype "bidirectional"))
    )
    (net (code "27") (name "/BP2_OUT") (class "Default")
      (node (ref "B2C2") (pin "1") (pinfunction "1_1") (pintype "passive"))
      (node (ref "U2") (pin "1") (pinfunction "A4_1") (pintype "bidirectional"))
      (node (ref "X8") (pin "1") (pinfunction "S_1") (pintype "passive"))
    )
    (net (code "28") (name "/BP2_POT1_IN") (class "Default")
      (node (ref "A") (pin "17") (pinfunction "VW1/RW1_17") (pintype "passive"))
      (node (ref "X7") (pin "2") (pinfunction "S_2") (pintype "passive"))
    )
    (net (code "29") (name "/BP2_POT1_OUT") (class "Default")
      (node (ref "A") (pin "16") (pinfunction "VH1/RH1_16") (pintype "passive"))
      (node (ref "X3") (pin "1") (pinfunction "S_1") (pintype "passive"))
    )
    (net (code "30") (name "/BP2_POT2_IN") (class "Default")
      (node (ref "A") (pin "21") (pinfunction "VH2/RH2_21") (pintype "passive"))
      (node (ref "X4") (pin "1") (pinfunction "S_1") (pintype "passive"))
    )
    (net (code "31") (name "/BP2_POT2_OUT") (class "Default")
      (node (ref "A") (pin "20") (pinfunction "VW2/RW2_20") (pintype "passive"))
      (node (ref "X8") (pin "2") (pinfunction "S_2") (pintype "passive"))
    )
    (net (code "32") (name "/BP6_AMP1_OUT") (class "Default")
      (node (ref "B6R3") (pin "1") (pinfunction "1_1") (pintype "passive"))
      (node (ref "IC2") (pin "1") (pinfunction "OUTA_1") (pintype "output"))
      (node (ref "X9") (pin "1") (pinfunction "S_1") (pintype "passive"))
    )
    (net (code "33") (name "/BP6_AMP2_OUT") (class "Default")
      (node (ref "B6C1") (pin "1") (pinfunction "1_1") (pintype "passive"))
      (node (ref "B6R4") (pin "1") (pinfunction "1_1") (pintype "passive"))
      (node (ref "IC2") (pin "7") (pinfunction "OUTB_7") (pintype "output"))
      (node (ref "X11") (pin "1") (pinfunction "S_1") (pintype "passive"))
    )
    (net (code "34") (name "/BP6_AMP3_OUT") (class "Default")
      (node (ref "B6C2") (pin "1") (pinfunction "1_1") (pintype "passive"))
      (node (ref "B6R1") (pin "1") (pinfunction "1_1") (pintype "passive"))
      (node (ref "IC2") (pin "14") (pinfunction "OUTD_14") (pintype "output"))
      (node (ref "X17") (pin "1") (pinfunction "S_1") (pintype "passive"))
    )
    (net (code "35") (name "/BP6_AMP4_OUT") (class "Default")
      (node (ref "B6C6") (pin "1") (pinfunction "1_1") (pintype "passive"))
      (node (ref "B6R7") (pin "1") (pinfunction "1_1") (pintype "passive"))
      (node (ref "IC3") (pin "1") (pinfunction "OUTA_1") (pintype "output"))
      (node (ref "X13") (pin "1") (pinfunction "S_1") (pintype "passive"))
    )
    (net (code "36") (name "/BP6_AMP5_OUT") (class "Default")
      (node (ref "B6C4") (pin "1") (pinfunction "1_1") (pintype "passive"))
      (node (ref "B6R8") (pin "1") (pinfunction "1_1") (pintype "passive"))
      (node (ref "IC3") (pin "7") (pinfunction "OUTB_7") (pintype "output"))
      (node (ref "X15") (pin "1") (pinfunction "S_1") (pintype "passive"))
    )
    (net (code "37") (name "/BP6_AMP6_OUT") (class "Default")
      (node (ref "B6C5") (pin "1") (pinfunction "1_1") (pintype "passive"))
      (node (ref "B6R5") (pin "1") (pinfunction "1_1") (pintype "passive"))
      (node (ref "IC3") (pin "14") (pinfunction "OUTD_14") (pintype "output"))
    )
    (net (code "38") (name "/BP6_BUFFER") (class "Default")
      (node (ref "B6C3") (pin "1") (pinfunction "1_1") (pintype "passive"))
      (node (ref "IC2") (pin "10") (pinfunction "+INC_10") (pintype "input"))
      (node (ref "X18") (pin "2") (pinfunction "S_2") (pintype "passive"))
    )
    (net (code "39") (name "/BP6_BUFFER_OUT") (class "Default")
      (node (ref "B6R6") (pin "2") (pinfunction "2_2") (pintype "passive"))
      (node (ref "IC2") (pin "8") (pinfunction "OUTC_8") (pintype "output"))
      (node (ref "IC2") (pin "9") (pinfunction "-INC_9") (pintype "input"))
    )
    (net (code "40") (name "/BP6_IN") (class "Default")
      (node (ref "B6R2") (pin "2") (pinfunction "2_2") (pintype "passive"))
      (node (ref "U1") (pin "5") (pinfunction "A5_5") (pintype "bidirectional"))
    )
    (net (code "41") (name "/BP6_OUT") (class "Default")
      (node (ref "B6C6") (pin "2") (pinfunction "2_2") (pintype "passive"))
      (node (ref "U2") (pin "5") (pinfunction "A5_5") (pintype "bidirectional"))
      (node (ref "X19") (pin "2") (pinfunction "S_2") (pintype "passive"))
    )
    (net (code "42") (name "/BP6_POT1_IN") (class "Default")
      (node (ref "B") (pin "3") (pinfunction "VW3/RW3_3") (pintype "passive"))
      (node (ref "X9") (pin "2") (pinfunction "S_2") (pintype "passive"))
    )
    (net (code "43") (name "/BP6_POT1_OUT") (class "Default")
      (node (ref "B") (pin "4") (pinfunction "VH3/RH3_4") (pintype "passive"))
      (node (ref "X10") (pin "1") (pinfunction "S_1") (pintype "passive"))
    )
    (net (code "44") (name "/BP6_POT2_IN") (class "Default")
      (node (ref "B") (pin "9") (pinfunction "VH0/RH0_9") (pintype "passive"))
      (node (ref "X11") (pin "2") (pinfunction "S_2") (pintype "passive"))
    )
    (net (code "45") (name "/BP6_POT2_OUT") (class "Default")
      (node (ref "B") (pin "10") (pinfunction "VW0/RW0_10") (pintype "passive"))
      (node (ref "X12") (pin "1") (pinfunction "S_1") (pintype "passive"))
    )
    (net (code "46") (name "/BP6_POT3_IN") (class "Default")
      (node (ref "B") (pin "21") (pinfunction "VH2/RH2_21") (pintype "passive"))
      (node (ref "X17") (pin "2") (pinfunction "S_2") (pintype "passive"))
    )
    (net (code "47") (name "/BP6_POT3_OUT") (class "Default")
      (node (ref "B") (pin "20") (pinfunction "VW2/RW2_20") (pintype "passive"))
      (node (ref "X18") (pin "1") (pinfunction "S_1") (pintype "passive"))
    )
    (net (code "48") (name "/BP6_POT4_IN") (class "Default")
      (node (ref "B") (pin "16") (pinfunction "VH1/RH1_16") (pintype "passive"))
      (node (ref "X13") (pin "2") (pinfunction "S_2") (pintype "passive"))
    )
    (net (code "49") (name "/BP6_POT4_OUT") (class "Default")
      (node (ref "B") (pin "17") (pinfunction "VW1/RW1_17") (pintype "passive"))
      (node (ref "X14") (pin "1") (pinfunction "S_1") (pintype "passive"))
    )
    (net (code "50") (name "/BP6_POT5_IN") (class "Default")
      (node (ref "C") (pin "3") (pinfunction "VW3/RW3_3") (pintype "passive"))
      (node (ref "X15") (pin "2") (pinfunction "S_2") (pintype "passive"))
    )
    (net (code "51") (name "/BP6_POT5_OUT") (class "Default")
      (node (ref "C") (pin "4") (pinfunction "VH3/RH3_4") (pintype "passive"))
      (node (ref "X16") (pin "1") (pinfunction "S_1") (pintype "passive"))
    )
    (net (code "52") (name "/BP6_POT6_IN") (class "Default")
      (node (ref "C") (pin "9") (pinfunction "VH0/RH0_9") (pintype "passive"))
      (node (ref "X19") (pin "1") (pinfunction "S_1") (pintype "passive"))
    )
    (net (code "53") (name "/BP6_POT6_OUT") (class "Default")
      (node (ref "C") (pin "10") (pinfunction "VW0/RW0_10") (pintype "passive"))
      (node (ref "X20") (pin "2") (pinfunction "S_2") (pintype "passive"))
    )
    (net (code "54") (name "/BUFFER1_OUT") (class "Default")
      (node (ref "IC1") (pin "6") (pinfunction "-INB_6") (pintype "input"))
      (node (ref "IC1") (pin "7") (pinfunction "OUTB_7") (pintype "output"))
      (node (ref "U1") (pin "3") (pinfunction "A_3") (pintype "bidirectional"))
    )
    (net (code "55") (name "/BUFFER2_IN") (class "Default")
      (node (ref "IC1") (pin "10") (pinfunction "+INC_10") (pintype "input"))
      (node (ref "U2") (pin "3") (pinfunction "A_3") (pintype "bidirectional"))
    )
    (net (code "56") (name "/GND") (class "Default")
      (node (ref "A") (pin "18") (pinfunction "VSS_18") (pintype "power_in"))
      (node (ref "B") (pin "18") (pinfunction "VSS_18") (pintype "power_in"))
      (node (ref "B2C2") (pin "2") (pinfunction "2_2") (pintype "passive"))
      (node (ref "B6C3") (pin "2") (pinfunction "2_2") (pintype "passive"))
      (node (ref "B6Q1") (pin "2") (pinfunction "2_2") (pintype "passive"))
      (node (ref "B6Q2") (pin "2") (pinfunction "2_2") (pintype "passive"))
      (node (ref "C") (pin "18") (pinfunction "VSS_18") (pintype "power_in"))
      (node (ref "C3") (pin "2") (pinfunction "2_2") (pintype "passive"))
      (node (ref "D") (pin "18") (pinfunction "VSS_18") (pintype "power_in"))
      (node (ref "HQ1") (pin "2") (pinfunction "2_2") (pintype "passive"))
      (node (ref "HQ2") (pin "2") (pinfunction "2_2") (pintype "passive"))
      (node (ref "HQ3") (pin "2") (pinfunction "2_2") (pintype "passive"))
      (node (ref "IC2") (pin "12") (pinfunction "+IND_12") (pintype "input"))
      (node (ref "IC2") (pin "5") (pinfunction "+INB_5") (pintype "input"))
      (node (ref "IC3") (pin "12") (pinfunction "+IND_12") (pintype "input"))
      (node (ref "IC3") (pin "5") (pinfunction "+INB_5") (pintype "input"))
      (node (ref "IC4") (pin "10") (pinfunction "+INC_10") (pintype "input"))
      (node (ref "IC4") (pin "3") (pinfunction "+INA_3") (pintype "input"))
      (node (ref "IC4") (pin "5") (pinfunction "+INB_5") (pintype "input"))
      (node (ref "IC5") (pin "10") (pinfunction "+INC_10") (pintype "input"))
      (node (ref "IC5") (pin "12") (pinfunction "+IND_12") (pintype "input"))
      (node (ref "IC5") (pin "3") (pinfunction "+INA_3") (pintype "input"))
      (node (ref "LPC") (pin "1") (pinfunction "1_1") (pintype "passive"))
      (node (ref "NR3") (pin "1") (pinfunction "1_1") (pintype "passive"))
      (node (ref "NR4") (pin "2") (pinfunction "2_2") (pintype "passive"))
      (node (ref "PA0") (pin "1") (pinfunction "1_1") (pintype "passive"))
      (node (ref "PA1") (pin "2") (pinfunction "2_2") (pintype "passive"))
      (node (ref "PA2") (pin "1") (pinfunction "1_1") (pintype "passive"))
      (node (ref "PA3") (pin "2") (pinfunction "2_2") (pintype "passive"))
      (node (ref "PB1") (pin "2") (pinfunction "2_2") (pintype "passive"))
      (node (ref "PB2") (pin "1") (pinfunction "1_1") (pintype "passive"))
      (node (ref "PB3") (pin "2") (pinfunction "2_2") (pintype "passive"))
      (node (ref "PC0") (pin "1") (pinfunction "1_1") (pintype "passive"))
      (node (ref "PC2") (pin "1") (pinfunction "1_1") (pintype "passive"))
      (node (ref "PC3") (pin "2") (pinfunction "2_2") (pintype "passive"))
      (node (ref "PD2") (pin "1") (pinfunction "1_1") (pintype "passive"))
      (node (ref "PD3") (pin "2") (pinfunction "2_2") (pintype "passive"))
      (node (ref "RE") (pin "2") (pinfunction "2_2") (pintype "passive"))
      (node (ref "RS0") (pin "2") (pinfunction "2_2") (pintype "passive"))
      (node (ref "RS1") (pin "2") (pinfunction "2_2") (pintype "passive"))
      (node (ref "RS2") (pin "2") (pinfunction "2_2") (pintype "passive"))
      (node (ref "S0-3R") (pin "2") (pinfunction "2_2") (pintype "passive"))
      (node (ref "SV1") (pin "4") (pinfunction "4_4") (pintype "passive"))
      (node (ref "SV1") (pin "6") (pinfunction "6_6") (pintype "passive"))
      (node (ref "U1") (pin "8") (pinfunction "GND_8") (pintype "power_in"))
      (node (ref "U2") (pin "8") (pinfunction "GND_8") (pintype "power_in"))
      (node (ref "U3") (pin "8") (pinfunction "GND_8") (pintype "power_in"))
      (node (ref "X1") (pin "2") (pinfunction "S_2") (pintype "passive"))
      (node (ref "X20") (pin "1") (pinfunction "S_1") (pintype "passive"))
      (node (ref "X3") (pin "2") (pinfunction "S_2") (pintype "passive"))
      (node (ref "X33") (pin "2") (pinfunction "S_2") (pintype "passive"))
      (node (ref "X34") (pin "2") (pinfunction "S_2") (pintype "passive"))
    )
    (net (code "57") (name "/HP1_IN") (class "Default")
      (node (ref "HPC") (pin "1") (pinfunction "1_1") (pintype "passive"))
      (node (ref "U1") (pin "15") (pinfunction "A2_15") (pintype "bidirectional"))
    )
    (net (code "58") (name "/HP1_OUT") (class "Default")
      (node (ref "HPC") (pin "2") (pinfunction "2_2") (pintype "passive"))
      (node (ref "U2") (pin "15") (pinfunction "A2_15") (pintype "bidirectional"))
      (node (ref "X2") (pin "1") (pinfunction "S_1") (pintype "passive"))
    )
    (net (code "59") (name "/HP1_POT_IN") (class "Default")
      (node (ref "A") (pin "3") (pinfunction "VW3/RW3_3") (pintype "passive"))
      (node (ref "X2") (pin "2") (pinfunction "S_2") (pintype "passive"))
    )
    (net (code "60") (name "/HP1_POT_OUT") (class "Default")
      (node (ref "A") (pin "4") (pinfunction "VH3/RH3_4") (pintype "passive"))
      (node (ref "X1") (pin "1") (pinfunction "S_1") (pintype "passive"))
    )
    (net (code "61") (name "/HP{slash}LP_AMP2_OUT") (class "Default")
      (node (ref "H/LC1") (pin "1") (pinfunction "1_1") (pintype "passive"))
      (node (ref "HLR4") (pin "1") (pinfunction "1_1") (pintype "passive"))
      (node (ref "IC4") (pin "1") (pinfunction "OUTA_1") (pintype "output"))
      (node (ref "X23") (pin "1") (pinfunction "S_1") (pintype "passive"))
    )
    (net (code "62") (name "/HP{slash}LP_AMP5_OUT") (class "Default")
      (node (ref "H/LC3") (pin "1") (pinfunction "1_1") (pintype "passive"))
      (node (ref "HLR8") (pin "1") (pinfunction "1_1") (pintype "passive"))
      (node (ref "IC4") (pin "8") (pinfunction "OUTC_8") (pintype "output"))
      (node (ref "X31") (pin "1") (pinfunction "S_1") (pintype "passive"))
    )
    (net (code "63") (name "/HP{slash}LP_AMP8_OUT") (class "Default")
      (node (ref "H/LC5") (pin "1") (pinfunction "1_1") (pintype "passive"))
      (node (ref "HLR12") (pin "1") (pinfunction "1_1") (pintype "passive"))
      (node (ref "IC5") (pin "14") (pinfunction "OUTD_14") (pintype "output"))
      (node (ref "X27") (pin "1") (pinfunction "S_1") (pintype "passive"))
    )
    (net (code "64") (name "/HP{slash}LP_HP_OUT1") (class "Default")
      (node (ref "HLR3") (pin "1") (pinfunction "1_1") (pintype "passive"))
      (node (ref "IC3") (pin "8") (pinfunction "OUTC_8") (pintype "output"))
      (node (ref "U3") (pin "12") (pinfunction "A0_12") (pintype "passive"))
      (node (ref "X21") (pin "1") (pinfunction "S_1") (pintype "passive"))
    )
    (net (code "65") (name "/HP{slash}LP_HP_OUT2") (class "Default")
      (node (ref "HLR7") (pin "1") (pinfunction "1_1") (pintype "passive"))
      (node (ref "IC4") (pin "14") (pinfunction "OUTD_14") (pintype "output"))
      (node (ref "U3") (pin "2") (pinfunction "B0_2") (pintype "passive"))
      (node (ref "X29") (pin "1") (pinfunction "S_1") (pintype "passive"))
    )
    (net (code "66") (name "/HP{slash}LP_HP_OUT3") (class "Default")
      (node (ref "HLR11") (pin "1") (pinfunction "1_1") (pintype "passive"))
      (node (ref "IC5") (pin "7") (pinfunction "OUTB_7") (pintype "output"))
      (node (ref "U3") (pin "5") (pinfunction "C0_5") (pintype "passive"))
      (node (ref "X25") (pin "1") (pinfunction "S_1") (pintype "passive"))
    )
    (net (code "67") (name "/HP{slash}LP_IN1") (class "Default")
      (node (ref "HLR1") (pin "2") (pinfunction "2_2") (pintype "passive"))
      (node (ref "U1") (pin "2") (pinfunction "A6_2") (pintype "bidirectional"))
    )
    (net (code "68") (name "/HP{slash}LP_IN2") (class "Default")
      (node (ref "HLR6") (pin "2") (pinfunction "2_2") (pintype "passive"))
      (node (ref "U3") (pin "14") (pinfunction "AN_14") (pintype "passive"))
    )
    (net (code "69") (name "/HP{slash}LP_IN3") (class "Default")
      (node (ref "HLR10") (pin "2") (pinfunction "2_2") (pintype "passive"))
      (node (ref "U3") (pin "15") (pinfunction "BN_15") (pintype "passive"))
    )
    (net (code "70") (name "/HP{slash}LP_LP_OUT1") (class "Default")
      (node (ref "H/LC2") (pin "1") (pinfunction "1_1") (pintype "passive"))
      (node (ref "HLR2") (pin "1") (pinfunction "1_1") (pintype "passive"))
      (node (ref "IC4") (pin "7") (pinfunction "OUTB_7") (pintype "output"))
      (node (ref "U3") (pin "13") (pinfunction "A1_13") (pintype "passive"))
    )
    (net (code "71") (name "/HP{slash}LP_LP_OUT2") (class "Default")
      (node (ref "H/LC4") (pin "1") (pinfunction "1_1") (pintype "passive"))
      (node (ref "HLR5") (pin "1") (pinfunction "1_1") (pintype "passive"))
      (node (ref "IC5") (pin "1") (pinfunction "OUTA_1") (pintype "output"))
      (node (ref "U3") (pin "1") (pinfunction "B1_1") (pintype "passive"))
    )
    (net (code "72") (name "/HP{slash}LP_LP_OUT3") (class "Default")
      (node (ref "H/LC6") (pin "1") (pinfunction "1_1") (pintype "passive"))
      (node (ref "HLR9") (pin "1") (pinfunction "1_1") (pintype "passive"))
      (node (ref "IC5") (pin "8") (pinfunction "OUTC_8") (pintype "output"))
      (node (ref "U3") (pin "3") (pinfunction "C1_3") (pintype "passive"))
    )
    (net (code "73") (name "/HP{slash}LP_OUT") (class "Default")
      (node (ref "U2") (pin "2") (pinfunction "A6_2") (pintype "bidirectional"))
      (node (ref "U3") (pin "4") (pinfunction "CN_4") (pintype "passive"))
    )
    (net (code "74") (name "/HP{slash}LP_POT1_IN") (class "Default")
      (node (ref "C") (pin "21") (pinfunction "VH2/RH2_21") (pintype "passive"))
      (node (ref "X21") (pin "2") (pinfunction "S_2") (pintype "passive"))
    )
    (net (code "75") (name "/HP{slash}LP_POT1_OUT") (class "Default")
      (node (ref "C") (pin "20") (pinfunction "VW2/RW2_20") (pintype "passive"))
      (node (ref "X22") (pin "1") (pinfunction "S_1") (pintype "passive"))
    )
    (net (code "76") (name "/HP{slash}LP_POT2_IN") (class "Default")
      (node (ref "C") (pin "17") (pinfunction "VW1/RW1_17") (pintype "passive"))
      (node (ref "X23") (pin "2") (pinfunction "S_2") (pintype "passive"))
    )
    (net (code "77") (name "/HP{slash}LP_POT2_OUT") (class "Default")
      (node (ref "C") (pin "16") (pinfunction "VH1/RH1_16") (pintype "passive"))
      (node (ref "X24") (pin "1") (pinfunction "S_1") (pintype "passive"))
    )
    (net (code "78") (name "/HP{slash}LP_POT3_IN") (class "Default")
      (node (ref "D") (pin "4") (pinfunction "VH3/RH3_4") (pintype "passive"))
      (node (ref "X29") (pin "2") (pinfunction "S_2") (pintype "passive"))
    )
    (net (code "79") (name "/HP{slash}LP_POT3_OUT") (class "Default")
      (node (ref "D") (pin "5") (pinfunction "VL3/RL3_5") (pintype "passive"))
      (node (ref "X30") (pin "1") (pinfunction "S_1") (pintype "passive"))
    )
    (net (code "80") (name "/HP{slash}LP_POT4_IN") (class "Default")
      (node (ref "D") (pin "9") (pinfunction "VH0/RH0_9") (pintype "passive"))
      (node (ref "X31") (pin "2") (pinfunction "S_2") (pintype "passive"))
    )
    (net (code "81") (name "/HP{slash}LP_POT4_OUT") (class "Default")
      (node (ref "D") (pin "10") (pinfunction "VW0/RW0_10") (pintype "passive"))
      (node (ref "X32") (pin "1") (pinfunction "S_1") (pintype "passive"))
    )
    (net (code "82") (name "/HP{slash}LP_POT5_IN") (class "Default")
      (node (ref "D") (pin "21") (pinfunction "VH2/RH2_21") (pintype "passive"))
      (node (ref "X25") (pin "2") (pinfunction "S_2") (pintype "passive"))
    )
    (net (code "83") (name "/HP{slash}LP_POT5_OUT") (class "Default")
      (node (ref "D") (pin "20") (pinfunction "VW2/RW2_20") (pintype "passive"))
      (node (ref "X26") (pin "1") (pinfunction "S_1") (pintype "passive"))
    )
    (net (code "84") (name "/HP{slash}LP_POT6_IN") (class "Default")
      (node (ref "D") (pin "17") (pinfunction "VW1/RW1_17") (pintype "passive"))
      (node (ref "X27") (pin "2") (pinfunction "S_2") (pintype "passive"))
    )
    (net (code "85") (name "/HP{slash}LP_POT6_OUT") (class "Default")
      (node (ref "D") (pin "16") (pinfunction "VH1/RH1_16") (pintype "passive"))
      (node (ref "X28") (pin "1") (pinfunction "S_1") (pintype "passive"))
    )
    (net (code "86") (name "/HP{slash}LP_TOGGLE") (class "Default")
      (node (ref "S0-3R") (pin "1") (pinfunction "1_1") (pintype "passive"))
      (node (ref "SV1") (pin "8") (pinfunction "8_8") (pintype "passive"))
      (node (ref "U3") (pin "10") (pinfunction "S1_10") (pintype "input"))
      (node (ref "U3") (pin "11") (pinfunction "S0_11") (pintype "input"))
      (node (ref "U3") (pin "9") (pinfunction "S2_9") (pintype "input"))
    )
    (net (code "87") (name "/LP1_IN") (class "Default")
      (node (ref "U1") (pin "12") (pinfunction "A3_12") (pintype "bidirectional"))
      (node (ref "X5") (pin "2") (pinfunction "S_2") (pintype "passive"))
    )
    (net (code "88") (name "/LP1_OUT") (class "Default")
      (node (ref "LPC") (pin "2") (pinfunction "2_2") (pintype "passive"))
      (node (ref "U2") (pin "12") (pinfunction "A3_12") (pintype "bidirectional"))
      (node (ref "X6") (pin "1") (pinfunction "S_1") (pintype "passive"))
    )
    (net (code "89") (name "/LP1_POT_IN") (class "Default")
      (node (ref "A") (pin "9") (pinfunction "VH0/RH0_9") (pintype "passive"))
      (node (ref "X5") (pin "1") (pinfunction "S_1") (pintype "passive"))
    )
    (net (code "90") (name "/LP1_POT_OUT") (class "Default")
      (node (ref "A") (pin "10") (pinfunction "VW0/RW0_10") (pintype "passive"))
      (node (ref "X6") (pin "2") (pinfunction "S_2") (pintype "passive"))
    )
    (net (code "91") (name "/NOTCH_IN") (class "Default")
      (node (ref "C1") (pin "1") (pinfunction "1_1") (pintype "passive"))
      (node (ref "NR1") (pin "2") (pinfunction "2_2") (pintype "passive"))
      (node (ref "U1") (pin "14") (pinfunction "A1_14") (pintype "bidirectional"))
    )
    (net (code "92") (name "/NOTCH_OUT") (class "Default")
      (node (ref "C2") (pin "2") (pinfunction "2_2") (pintype "passive"))
      (node (ref "NR2") (pin "1") (pinfunction "1_1") (pintype "passive"))
      (node (ref "NR4") (pin "1") (pinfunction "1_1") (pintype "passive"))
      (node (ref "U2") (pin "14") (pinfunction "A1_14") (pintype "bidirectional"))
    )
    (net (code "93") (name "/PASS") (class "Default")
      (node (ref "U1") (pin "13") (pinfunction "A0_13") (pintype "bidirectional"))
      (node (ref "U2") (pin "13") (pinfunction "A0_13") (pintype "bidirectional"))
    )
    (net (code "94") (name "/SCL") (class "Default")
      (node (ref "A") (pin "23") (pinfunction "SCL_23") (pintype "passive"))
      (node (ref "B") (pin "23") (pinfunction "SCL_23") (pintype "passive"))
      (node (ref "C") (pin "23") (pinfunction "SCL_23") (pintype "passive"))
      (node (ref "D") (pin "23") (pinfunction "SCL_23") (pintype "passive"))
      (node (ref "SCLR") (pin "2") (pinfunction "2_2") (pintype "passive"))
      (node (ref "SV1") (pin "12") (pinfunction "12_12") (pintype "passive"))
    )
    (net (code "95") (name "/SDA") (class "Default")
      (node (ref "A") (pin "13") (pinfunction "SDA_13") (pintype "passive"))
      (node (ref "B") (pin "13") (pinfunction "SDA_13") (pintype "passive"))
      (node (ref "C") (pin "13") (pinfunction "SDA_13") (pintype "passive"))
      (node (ref "D") (pin "13") (pinfunction "SDA_13") (pintype "passive"))
      (node (ref "SDAR") (pin "2") (pinfunction "2_2") (pintype "passive"))
      (node (ref "SV1") (pin "2") (pinfunction "2_2") (pintype "passive"))
    )
    (net (code "96") (name "/SYSTEM_0") (class "Default")
      (node (ref "RS0") (pin "1") (pinfunction "1_1") (pintype "passive"))
      (node (ref "SV1") (pin "5") (pinfunction "5_5") (pintype "passive"))
      (node (ref "U1") (pin "11") (pinfunction "S0_11") (pintype "output"))
      (node (ref "U2") (pin "11") (pinfunction "S0_11") (pintype "output"))
    )
    (net (code "97") (name "/SYSTEM_1") (class "Default")
      (node (ref "RS1") (pin "1") (pinfunction "1_1") (pintype "passive"))
      (node (ref "SV1") (pin "7") (pinfunction "7_7") (pintype "passive"))
      (node (ref "U1") (pin "10") (pinfunction "S1_10") (pintype "output"))
      (node (ref "U2") (pin "10") (pinfunction "S1_10") (pintype "output"))
    )
    (net (code "98") (name "/SYSTEM_2") (class "Default")
      (node (ref "RS2") (pin "1") (pinfunction "1_1") (pintype "passive"))
      (node (ref "SV1") (pin "9") (pinfunction "9_9") (pintype "passive"))
      (node (ref "U1") (pin "9") (pinfunction "S2_9") (pintype "output"))
      (node (ref "U2") (pin "9") (pinfunction "S2_9") (pintype "output"))
    )
    (net (code "99") (name "/SYSTEM_E") (class "Default")
      (node (ref "RE") (pin "1") (pinfunction "1_1") (pintype "passive"))
      (node (ref "SV1") (pin "3") (pinfunction "3_3") (pintype "passive"))
      (node (ref "U1") (pin "6") (pinfunction "~{E}_6") (pintype "input"))
      (node (ref "U2") (pin "6") (pinfunction "~{E}_6") (pintype "input"))
      (node (ref "U3") (pin "6") (pinfunction "~{E}_6") (pintype "passive"))
    )
    (net (code "100") (name "/SYSTEM_IN") (class "Default")
      (node (ref "IC1") (pin "5") (pinfunction "+INB_5") (pintype "input"))
      (node (ref "X34") (pin "1") (pinfunction "S_1") (pintype "passive"))
    )
    (net (code "101") (name "/SYSTEM_OUT") (class "Default")
      (node (ref "IC1") (pin "8") (pinfunction "OUTC_8") (pintype "output"))
      (node (ref "IC1") (pin "9") (pinfunction "-INC_9") (pintype "input"))
      (node (ref "X33") (pin "1") (pinfunction "S_1") (pintype "passive"))
    )
    (net (code "102") (name "Net-(A-A0)") (class "Default")
      (node (ref "A") (pin "2") (pinfunction "A0_2") (pintype "passive"))
      (node (ref "PA0") (pin "2") (pinfunction "2_2") (pintype "passive"))
    )
    (net (code "103") (name "Net-(A-A1)") (class "Default")
      (node (ref "A") (pin "14") (pinfunction "A1_14") (pintype "passive"))
      (node (ref "PA1") (pin "1") (pinfunction "1_1") (pintype "passive"))
    )
    (net (code "104") (name "Net-(A-A2)") (class "Default")
      (node (ref "A") (pin "11") (pinfunction "A2_11") (pintype "passive"))
      (node (ref "PA2") (pin "2") (pinfunction "2_2") (pintype "passive"))
    )
    (net (code "105") (name "Net-(A-A3)") (class "Default")
      (node (ref "A") (pin "24") (pinfunction "A3_24") (pintype "passive"))
      (node (ref "PA3") (pin "1") (pinfunction "1_1") (pintype "passive"))
    )
    (net (code "106") (name "Net-(B-A0)") (class "Default")
      (node (ref "B") (pin "2") (pinfunction "A0_2") (pintype "passive"))
      (node (ref "PB0") (pin "2") (pinfunction "2_2") (pintype "passive"))
    )
    (net (code "107") (name "Net-(B-A1)") (class "Default")
      (node (ref "B") (pin "14") (pinfunction "A1_14") (pintype "passive"))
      (node (ref "PB1") (pin "1") (pinfunction "1_1") (pintype "passive"))
    )
    (net (code "108") (name "Net-(B-A2)") (class "Default")
      (node (ref "B") (pin "11") (pinfunction "A2_11") (pintype "passive"))
      (node (ref "PB2") (pin "2") (pinfunction "2_2") (pintype "passive"))
    )
    (net (code "109") (name "Net-(B-A3)") (class "Default")
      (node (ref "B") (pin "24") (pinfunction "A3_24") (pintype "passive"))
      (node (ref "PB3") (pin "1") (pinfunction "1_1") (pintype "passive"))
    )
    (net (code "110") (name "Net-(C-A0)") (class "Default")
      (node (ref "C") (pin "2") (pinfunction "A0_2") (pintype "passive"))
      (node (ref "PC0") (pin "2") (pinfunction "2_2") (pintype "passive"))
    )
    (net (code "111") (name "Net-(C-A1)") (class "Default")
      (node (ref "C") (pin "14") (pinfunction "A1_14") (pintype "passive"))
      (node (ref "PC1") (pin "1") (pinfunction "1_1") (pintype "passive"))
    )
    (net (code "112") (name "Net-(C-A2)") (class "Default")
      (node (ref "C") (pin "11") (pinfunction "A2_11") (pintype "passive"))
      (node (ref "PC2") (pin "2") (pinfunction "2_2") (pintype "passive"))
    )
    (net (code "113") (name "Net-(C-A3)") (class "Default")
      (node (ref "C") (pin "24") (pinfunction "A3_24") (pintype "passive"))
      (node (ref "PC3") (pin "1") (pinfunction "1_1") (pintype "passive"))
    )
    (net (code "114") (name "Net-(C1-Pad2)") (class "Default")
      (node (ref "C1") (pin "2") (pinfunction "2_2") (pintype "passive"))
      (node (ref "C2") (pin "1") (pinfunction "1_1") (pintype "passive"))
      (node (ref "NR3") (pin "2") (pinfunction "2_2") (pintype "passive"))
    )
    (net (code "115") (name "Net-(C3-Pad1)") (class "Default")
      (node (ref "C3") (pin "1") (pinfunction "1_1") (pintype "passive"))
      (node (ref "NR1") (pin "1") (pinfunction "1_1") (pintype "passive"))
      (node (ref "NR2") (pin "2") (pinfunction "2_2") (pintype "passive"))
    )
    (net (code "116") (name "Net-(D-A0)") (class "Default")
      (node (ref "D") (pin "2") (pinfunction "A0_2") (pintype "passive"))
      (node (ref "PD0") (pin "2") (pinfunction "2_2") (pintype "passive"))
    )
    (net (code "117") (name "Net-(D-A1)") (class "Default")
      (node (ref "D") (pin "14") (pinfunction "A1_14") (pintype "passive"))
      (node (ref "PD1") (pin "1") (pinfunction "1_1") (pintype "passive"))
    )
    (net (code "118") (name "Net-(D-A2)") (class "Default")
      (node (ref "D") (pin "11") (pinfunction "A2_11") (pintype "passive"))
      (node (ref "PD2") (pin "2") (pinfunction "2_2") (pintype "passive"))
    )
    (net (code "119") (name "Net-(D-A3)") (class "Default")
      (node (ref "D") (pin "24") (pinfunction "A3_24") (pintype "passive"))
      (node (ref "PD3") (pin "1") (pinfunction "1_1") (pintype "passive"))
    )
    (net (code "120") (name "unconnected-(A-NC-Pad1)") (class "Default")
      (node (ref "A") (pin "1") (pinfunction "NC_1") (pintype "no_connect"))
    )
    (net (code "121") (name "unconnected-(A-VL0{slash}RL0-Pad8)") (class "Default")
      (node (ref "A") (pin "8") (pinfunction "VL0/RL0_8") (pintype "passive"))
    )
    (net (code "122") (name "unconnected-(A-VL1{slash}RW1-Pad15)") (class "Default")
      (node (ref "A") (pin "15") (pinfunction "VL1/RW1_15") (pintype "passive"))
    )
    (net (code "123") (name "unconnected-(A-VL2{slash}RL2-Pad22)") (class "Default")
      (node (ref "A") (pin "22") (pinfunction "VL2/RL2_22") (pintype "passive"))
    )
    (net (code "124") (name "unconnected-(A-VL3{slash}RL3-Pad5)") (class "Default")
      (node (ref "A") (pin "5") (pinfunction "VL3/RL3_5") (pintype "passive"))
    )
    (net (code "125") (name "unconnected-(A-~{WP}-Pad12)") (class "Default")
      (node (ref "A") (pin "12") (pinfunction "~{WP}_12") (pintype "passive"))
    )
    (net (code "126") (name "unconnected-(B-NC-Pad1)") (class "Default")
      (node (ref "B") (pin "1") (pinfunction "NC_1") (pintype "no_connect"))
    )
    (net (code "127") (name "unconnected-(B-VL0{slash}RL0-Pad8)") (class "Default")
      (node (ref "B") (pin "8") (pinfunction "VL0/RL0_8") (pintype "passive"))
    )
    (net (code "128") (name "unconnected-(B-VL1{slash}RW1-Pad15)") (class "Default")
      (node (ref "B") (pin "15") (pinfunction "VL1/RW1_15") (pintype "passive"))
    )
    (net (code "129") (name "unconnected-(B-VL2{slash}RL2-Pad22)") (class "Default")
      (node (ref "B") (pin "22") (pinfunction "VL2/RL2_22") (pintype "passive"))
    )
    (net (code "130") (name "unconnected-(B-VL3{slash}RL3-Pad5)") (class "Default")
      (node (ref "B") (pin "5") (pinfunction "VL3/RL3_5") (pintype "passive"))
    )
    (net (code "131") (name "unconnected-(B-~{WP}-Pad12)") (class "Default")
      (node (ref "B") (pin "12") (pinfunction "~{WP}_12") (pintype "passive"))
    )
    (net (code "132") (name "unconnected-(C-NC-Pad1)") (class "Default")
      (node (ref "C") (pin "1") (pinfunction "NC_1") (pintype "no_connect"))
    )
    (net (code "133") (name "unconnected-(C-VL0{slash}RL0-Pad8)") (class "Default")
      (node (ref "C") (pin "8") (pinfunction "VL0/RL0_8") (pintype "passive"))
    )
    (net (code "134") (name "unconnected-(C-VL1{slash}RW1-Pad15)") (class "Default")
      (node (ref "C") (pin "15") (pinfunction "VL1/RW1_15") (pintype "passive"))
    )
    (net (code "135") (name "unconnected-(C-VL2{slash}RL2-Pad22)") (class "Default")
      (node (ref "C") (pin "22") (pinfunction "VL2/RL2_22") (pintype "passive"))
    )
    (net (code "136") (name "unconnected-(C-VL3{slash}RL3-Pad5)") (class "Default")
      (node (ref "C") (pin "5") (pinfunction "VL3/RL3_5") (pintype "passive"))
    )
    (net (code "137") (name "unconnected-(C-~{WP}-Pad12)") (class "Default")
      (node (ref "C") (pin "12") (pinfunction "~{WP}_12") (pintype "passive"))
    )
    (net (code "138") (name "unconnected-(D-NC-Pad1)") (class "Default")
      (node (ref "D") (pin "1") (pinfunction "NC_1") (pintype "no_connect"))
    )
    (net (code "139") (name "unconnected-(D-VL0{slash}RL0-Pad8)") (class "Default")
      (node (ref "D") (pin "8") (pinfunction "VL0/RL0_8") (pintype "passive"))
    )
    (net (code "140") (name "unconnected-(D-VL1{slash}RW1-Pad15)") (class "Default")
      (node (ref "D") (pin "15") (pinfunction "VL1/RW1_15") (pintype "passive"))
    )
    (net (code "141") (name "unconnected-(D-VL2{slash}RL2-Pad22)") (class "Default")
      (node (ref "D") (pin "22") (pinfunction "VL2/RL2_22") (pintype "passive"))
    )
    (net (code "142") (name "unconnected-(D-VW3{slash}RW3-Pad3)") (class "Default")
      (node (ref "D") (pin "3") (pinfunction "VW3/RW3_3") (pintype "passive"))
    )
    (net (code "143") (name "unconnected-(D-~{WP}-Pad12)") (class "Default")
      (node (ref "D") (pin "12") (pinfunction "~{WP}_12") (pintype "passive"))
    )
    (net (code "144") (name "unconnected-(IC1-+INA-Pad3)") (class "Default")
      (node (ref "IC1") (pin "3") (pinfunction "+INA_3") (pintype "input"))
    )
    (net (code "145") (name "unconnected-(IC1--INA-Pad2)") (class "Default")
      (node (ref "IC1") (pin "2") (pinfunction "-INA_2") (pintype "input"))
    )
    (net (code "146") (name "unconnected-(IC1-OUTA-Pad1)") (class "Default")
      (node (ref "IC1") (pin "1") (pinfunction "OUTA_1") (pintype "output"))
    )
    (net (code "147") (name "unconnected-(U1-A7-Pad4)") (class "Default")
      (node (ref "U1") (pin "4") (pinfunction "A7_4") (pintype "bidirectional"))
    )
    (net (code "148") (name "unconnected-(U2-A7-Pad4)") (class "Default")
      (node (ref "U2") (pin "4") (pinfunction "A7_4") (pintype "bidirectional"))
    )
  )
)
